# HighVoltageMeasurementModule_1000V_multi.net
KiCad netlist of a schematic drawn in EAGLE
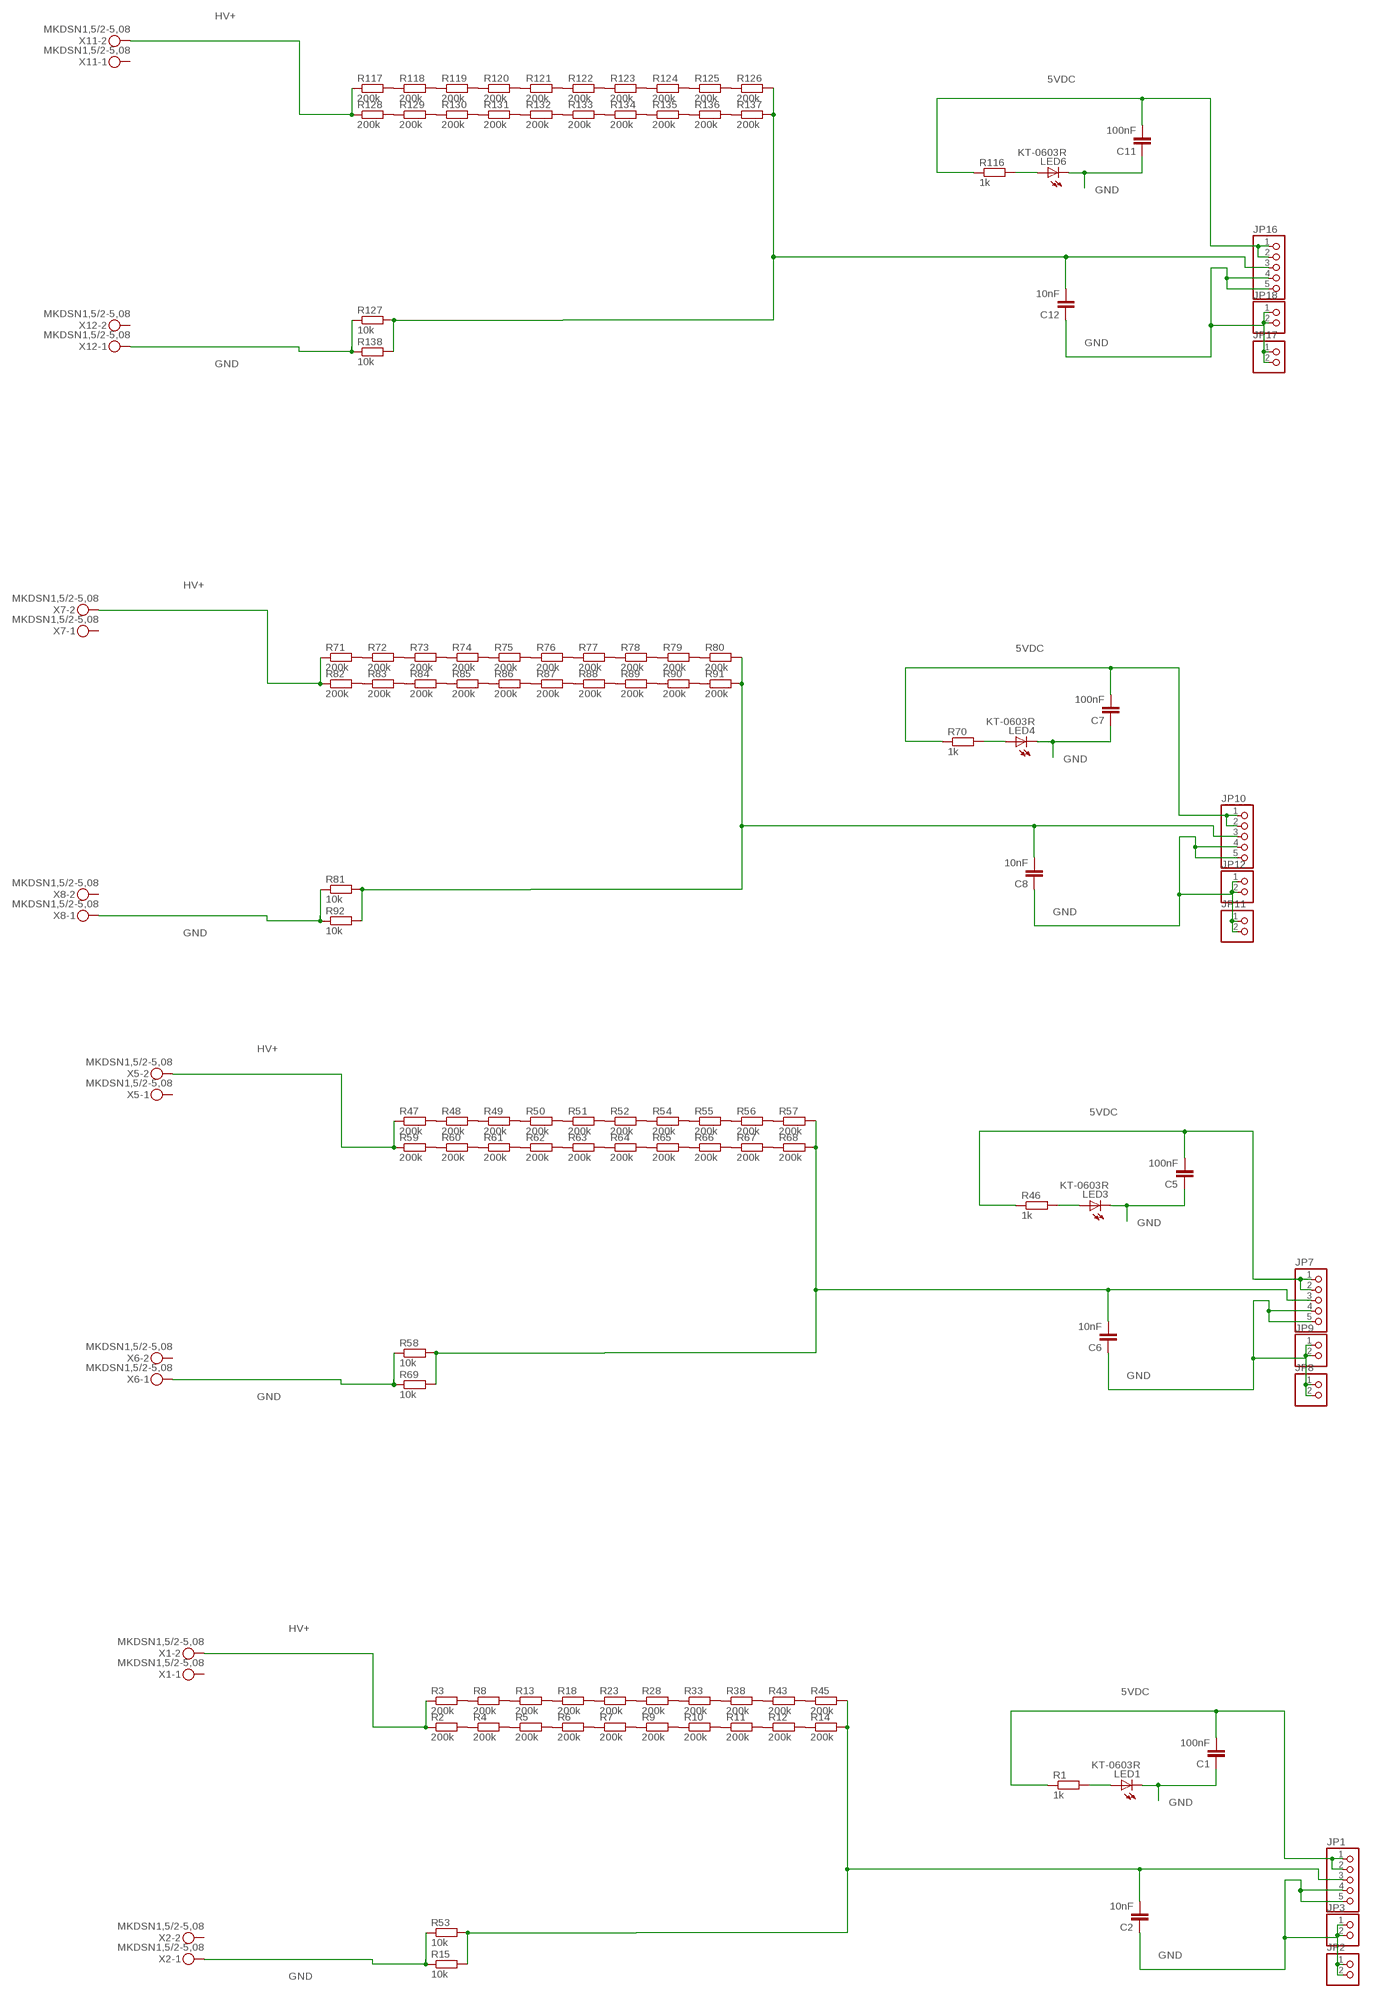
[diagram p0: schematic, sheet 1, part 1 of 2]
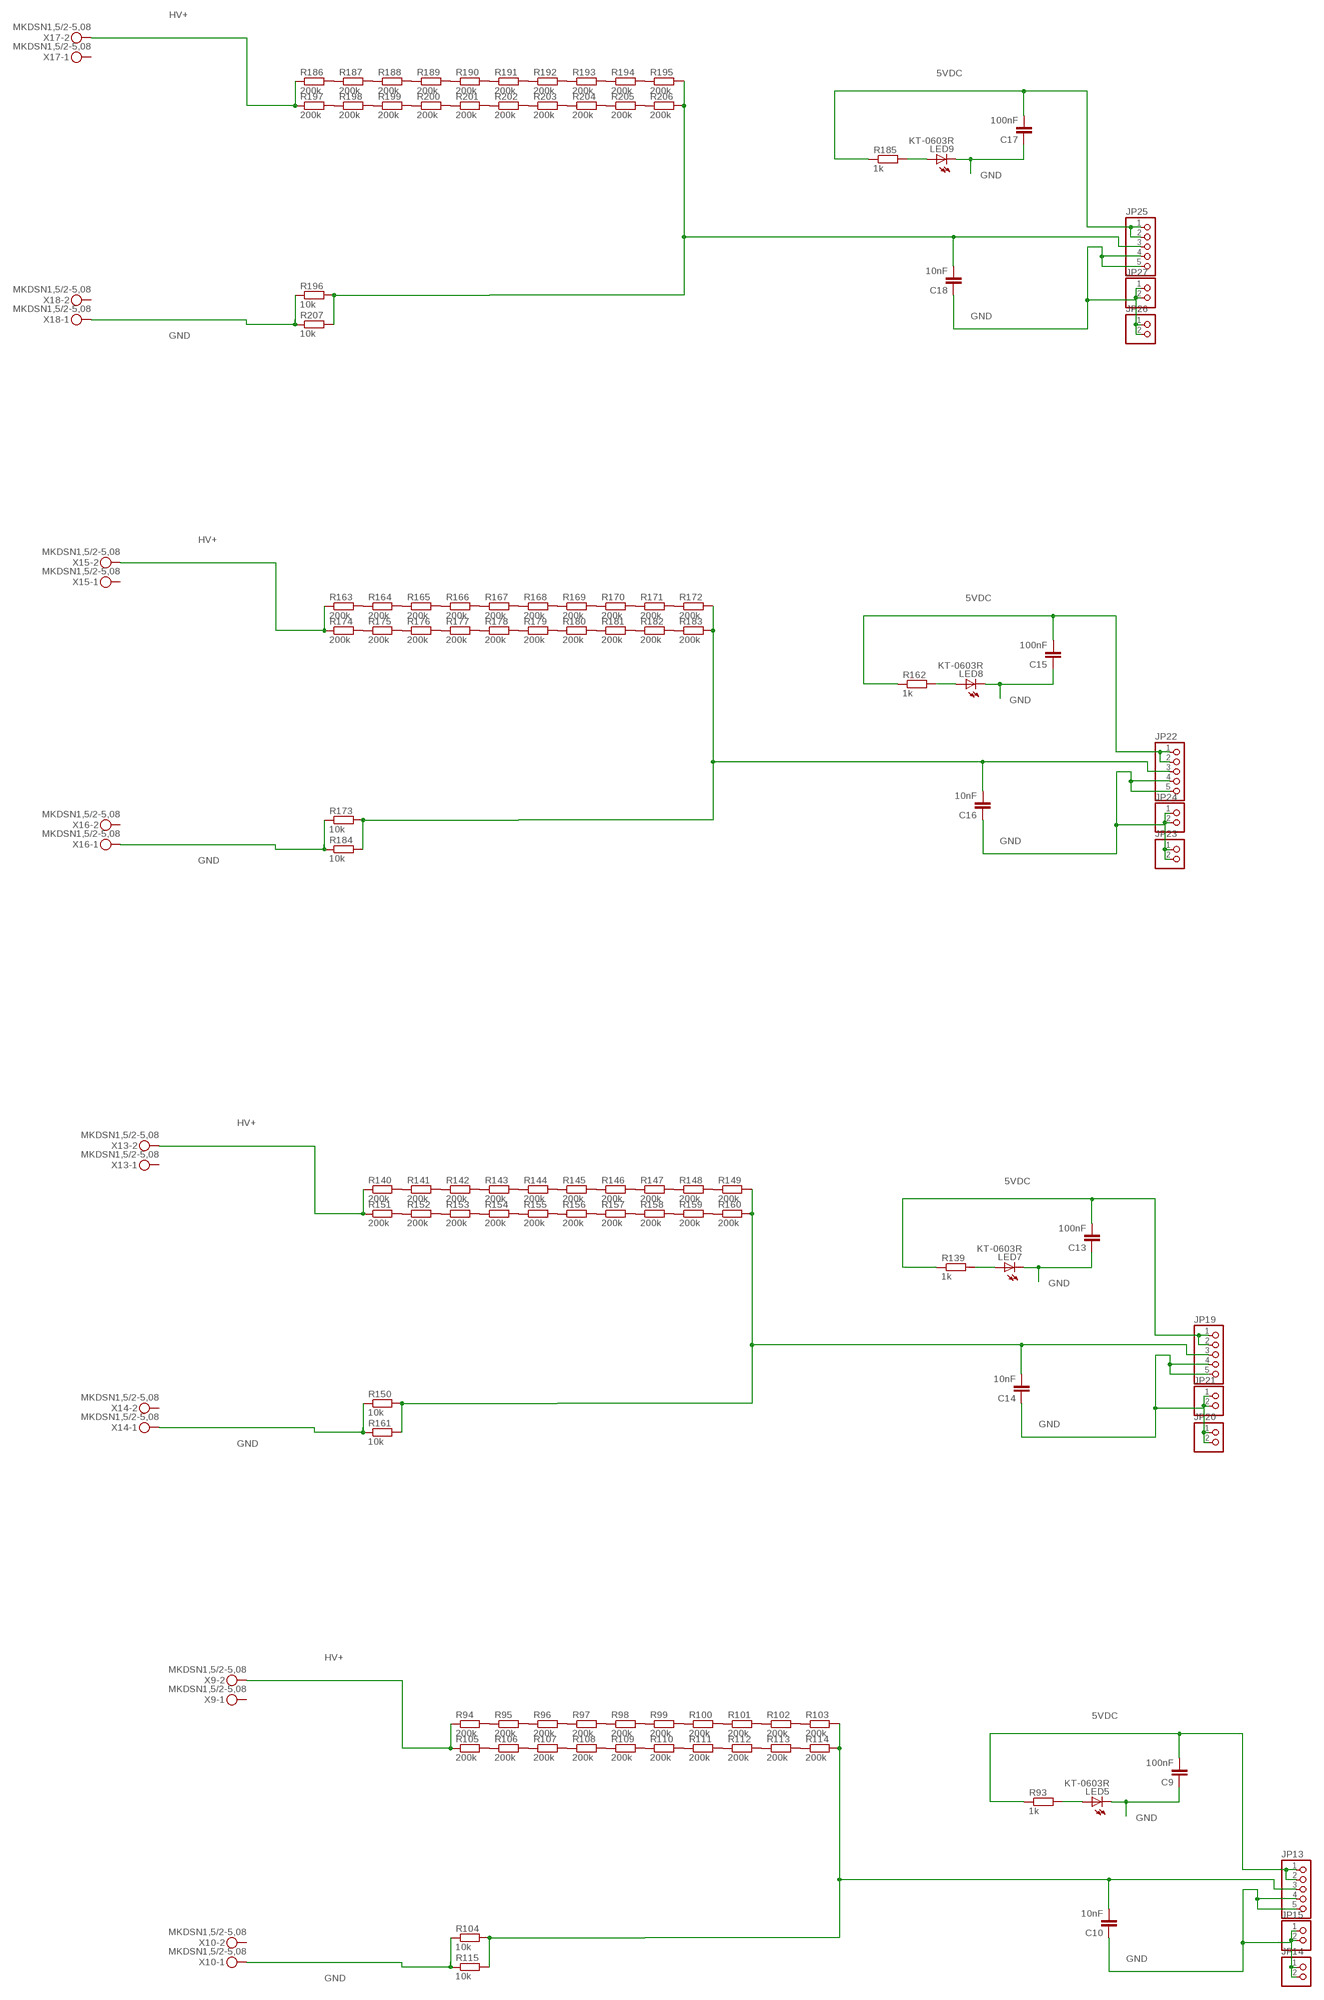
[diagram p1: schematic, sheet 1, part 2 of 2]

(export (version "E")
  (design (tool "Eeschema 10.0.6"))
  (components
    (comp (ref "C1")
      (value "100nF")
      (footprint "eagle-import:C0805")
      (libsource (lib "eagle-import") (part "C-EUC0805"))
    )
    (comp (ref "C2")
      (value "10nF")
      (footprint "eagle-import:C0805")
      (libsource (lib "eagle-import") (part "C-EUC0805"))
    )
    (comp (ref "C5")
      (value "100nF")
      (footprint "eagle-import:C0805")
      (libsource (lib "eagle-import") (part "C-EUC0805"))
    )
    (comp (ref "C6")
      (value "10nF")
      (footprint "eagle-import:C0805")
      (libsource (lib "eagle-import") (part "C-EUC0805"))
    )
    (comp (ref "C7")
      (value "100nF")
      (footprint "eagle-import:C0805")
      (libsource (lib "eagle-import") (part "C-EUC0805"))
    )
    (comp (ref "C8")
      (value "10nF")
      (footprint "eagle-import:C0805")
      (libsource (lib "eagle-import") (part "C-EUC0805"))
    )
    (comp (ref "C9")
      (value "100nF")
      (footprint "eagle-import:C0805")
      (libsource (lib "eagle-import") (part "C-EUC0805"))
    )
    (comp (ref "C10")
      (value "10nF")
      (footprint "eagle-import:C0805")
      (libsource (lib "eagle-import") (part "C-EUC0805"))
    )
    (comp (ref "C11")
      (value "100nF")
      (footprint "eagle-import:C0805")
      (libsource (lib "eagle-import") (part "C-EUC0805"))
    )
    (comp (ref "C12")
      (value "10nF")
      (footprint "eagle-import:C0805")
      (libsource (lib "eagle-import") (part "C-EUC0805"))
    )
    (comp (ref "C13")
      (value "100nF")
      (footprint "eagle-import:C0805")
      (libsource (lib "eagle-import") (part "C-EUC0805"))
    )
    (comp (ref "C14")
      (value "10nF")
      (footprint "eagle-import:C0805")
      (libsource (lib "eagle-import") (part "C-EUC0805"))
    )
    (comp (ref "C15")
      (value "100nF")
      (footprint "eagle-import:C0805")
      (libsource (lib "eagle-import") (part "C-EUC0805"))
    )
    (comp (ref "C16")
      (value "10nF")
      (footprint "eagle-import:C0805")
      (libsource (lib "eagle-import") (part "C-EUC0805"))
    )
    (comp (ref "C17")
      (value "100nF")
      (footprint "eagle-import:C0805")
      (libsource (lib "eagle-import") (part "C-EUC0805"))
    )
    (comp (ref "C18")
      (value "10nF")
      (footprint "eagle-import:C0805")
      (libsource (lib "eagle-import") (part "C-EUC0805"))
    )
    (comp (ref "JP1")
      (value "PINHD-1X5")
      (footprint "eagle-import:1X05")
      (libsource (lib "eagle-import") (part "PINHD-1X5"))
    )
    (comp (ref "JP2")
      (value "PINHD-1X2")
      (footprint "eagle-import:1X02")
      (libsource (lib "eagle-import") (part "PINHD-1X2"))
    )
    (comp (ref "JP3")
      (value "PINHD-1X2")
      (footprint "eagle-import:1X02")
      (libsource (lib "eagle-import") (part "PINHD-1X2"))
    )
    (comp (ref "JP7")
      (value "PINHD-1X5")
      (footprint "eagle-import:1X05")
      (libsource (lib "eagle-import") (part "PINHD-1X5"))
    )
    (comp (ref "JP8")
      (value "PINHD-1X2")
      (footprint "eagle-import:1X02")
      (libsource (lib "eagle-import") (part "PINHD-1X2"))
    )
    (comp (ref "JP9")
      (value "PINHD-1X2")
      (footprint "eagle-import:1X02")
      (libsource (lib "eagle-import") (part "PINHD-1X2"))
    )
    (comp (ref "JP10")
      (value "PINHD-1X5")
      (footprint "eagle-import:1X05")
      (libsource (lib "eagle-import") (part "PINHD-1X5"))
    )
    (comp (ref "JP11")
      (value "PINHD-1X2")
      (footprint "eagle-import:1X02")
      (libsource (lib "eagle-import") (part "PINHD-1X2"))
    )
    (comp (ref "JP12")
      (value "PINHD-1X2")
      (footprint "eagle-import:1X02")
      (libsource (lib "eagle-import") (part "PINHD-1X2"))
    )
    (comp (ref "JP13")
      (value "PINHD-1X5")
      (footprint "eagle-import:1X05")
      (libsource (lib "eagle-import") (part "PINHD-1X5"))
    )
    (comp (ref "JP14")
      (value "PINHD-1X2")
      (footprint "eagle-import:1X02")
      (libsource (lib "eagle-import") (part "PINHD-1X2"))
    )
    (comp (ref "JP15")
      (value "PINHD-1X2")
      (footprint "eagle-import:1X02")
      (libsource (lib "eagle-import") (part "PINHD-1X2"))
    )
    (comp (ref "JP16")
      (value "PINHD-1X5")
      (footprint "eagle-import:1X05")
      (libsource (lib "eagle-import") (part "PINHD-1X5"))
    )
    (comp (ref "JP17")
      (value "PINHD-1X2")
      (footprint "eagle-import:1X02")
      (libsource (lib "eagle-import") (part "PINHD-1X2"))
    )
    (comp (ref "JP18")
      (value "PINHD-1X2")
      (footprint "eagle-import:1X02")
      (libsource (lib "eagle-import") (part "PINHD-1X2"))
    )
    (comp (ref "JP19")
      (value "PINHD-1X5")
      (footprint "eagle-import:1X05")
      (libsource (lib "eagle-import") (part "PINHD-1X5"))
    )
    (comp (ref "JP20")
      (value "PINHD-1X2")
      (footprint "eagle-import:1X02")
      (libsource (lib "eagle-import") (part "PINHD-1X2"))
    )
    (comp (ref "JP21")
      (value "PINHD-1X2")
      (footprint "eagle-import:1X02")
      (libsource (lib "eagle-import") (part "PINHD-1X2"))
    )
    (comp (ref "JP22")
      (value "PINHD-1X5")
      (footprint "eagle-import:1X05")
      (libsource (lib "eagle-import") (part "PINHD-1X5"))
    )
    (comp (ref "JP23")
      (value "PINHD-1X2")
      (footprint "eagle-import:1X02")
      (libsource (lib "eagle-import") (part "PINHD-1X2"))
    )
    (comp (ref "JP24")
      (value "PINHD-1X2")
      (footprint "eagle-import:1X02")
      (libsource (lib "eagle-import") (part "PINHD-1X2"))
    )
    (comp (ref "JP25")
      (value "PINHD-1X5")
      (footprint "eagle-import:1X05")
      (libsource (lib "eagle-import") (part "PINHD-1X5"))
    )
    (comp (ref "JP26")
      (value "PINHD-1X2")
      (footprint "eagle-import:1X02")
      (libsource (lib "eagle-import") (part "PINHD-1X2"))
    )
    (comp (ref "JP27")
      (value "PINHD-1X2")
      (footprint "eagle-import:1X02")
      (libsource (lib "eagle-import") (part "PINHD-1X2"))
    )
    (comp (ref "LED1")
      (value "KT-0603R")
      (footprint "eagle-import:CHIPLED_0603")
      (libsource (lib "eagle-import") (part "LEDCHIPLED_0603"))
    )
    (comp (ref "LED3")
      (value "KT-0603R")
      (footprint "eagle-import:CHIPLED_0603")
      (libsource (lib "eagle-import") (part "LEDCHIPLED_0603"))
    )
    (comp (ref "LED4")
      (value "KT-0603R")
      (footprint "eagle-import:CHIPLED_0603")
      (libsource (lib "eagle-import") (part "LEDCHIPLED_0603"))
    )
    (comp (ref "LED5")
      (value "KT-0603R")
      (footprint "eagle-import:CHIPLED_0603")
      (libsource (lib "eagle-import") (part "LEDCHIPLED_0603"))
    )
    (comp (ref "LED6")
      (value "KT-0603R")
      (footprint "eagle-import:CHIPLED_0603")
      (libsource (lib "eagle-import") (part "LEDCHIPLED_0603"))
    )
    (comp (ref "LED7")
      (value "KT-0603R")
      (footprint "eagle-import:CHIPLED_0603")
      (libsource (lib "eagle-import") (part "LEDCHIPLED_0603"))
    )
    (comp (ref "LED8")
      (value "KT-0603R")
      (footprint "eagle-import:CHIPLED_0603")
      (libsource (lib "eagle-import") (part "LEDCHIPLED_0603"))
    )
    (comp (ref "LED9")
      (value "KT-0603R")
      (footprint "eagle-import:CHIPLED_0603")
      (libsource (lib "eagle-import") (part "LEDCHIPLED_0603"))
    )
    (comp (ref "R1")
      (value "1k")
      (footprint "eagle-import:R0805")
      (libsource (lib "eagle-import") (part "R-EU_R0805"))
    )
    (comp (ref "R2")
      (value "200k")
      (footprint "eagle-import:R0805")
      (libsource (lib "eagle-import") (part "R-EU_R0805"))
    )
    (comp (ref "R3")
      (value "200k")
      (footprint "eagle-import:R0805")
      (libsource (lib "eagle-import") (part "R-EU_R0805"))
    )
    (comp (ref "R4")
      (value "200k")
      (footprint "eagle-import:R0805")
      (libsource (lib "eagle-import") (part "R-EU_R0805"))
    )
    (comp (ref "R5")
      (value "200k")
      (footprint "eagle-import:R0805")
      (libsource (lib "eagle-import") (part "R-EU_R0805"))
    )
    (comp (ref "R6")
      (value "200k")
      (footprint "eagle-import:R0805")
      (libsource (lib "eagle-import") (part "R-EU_R0805"))
    )
    (comp (ref "R7")
      (value "200k")
      (footprint "eagle-import:R0805")
      (libsource (lib "eagle-import") (part "R-EU_R0805"))
    )
    (comp (ref "R8")
      (value "200k")
      (footprint "eagle-import:R0805")
      (libsource (lib "eagle-import") (part "R-EU_R0805"))
    )
    (comp (ref "R9")
      (value "200k")
      (footprint "eagle-import:R0805")
      (libsource (lib "eagle-import") (part "R-EU_R0805"))
    )
    (comp (ref "R10")
      (value "200k")
      (footprint "eagle-import:R0805")
      (libsource (lib "eagle-import") (part "R-EU_R0805"))
    )
    (comp (ref "R11")
      (value "200k")
      (footprint "eagle-import:R0805")
      (libsource (lib "eagle-import") (part "R-EU_R0805"))
    )
    (comp (ref "R12")
      (value "200k")
      (footprint "eagle-import:R0805")
      (libsource (lib "eagle-import") (part "R-EU_R0805"))
    )
    (comp (ref "R13")
      (value "200k")
      (footprint "eagle-import:R0805")
      (libsource (lib "eagle-import") (part "R-EU_R0805"))
    )
    (comp (ref "R14")
      (value "200k")
      (footprint "eagle-import:R0805")
      (libsource (lib "eagle-import") (part "R-EU_R0805"))
    )
    (comp (ref "R15")
      (value "10k")
      (footprint "eagle-import:R0805")
      (libsource (lib "eagle-import") (part "R-EU_R0805"))
    )
    (comp (ref "R18")
      (value "200k")
      (footprint "eagle-import:R0805")
      (libsource (lib "eagle-import") (part "R-EU_R0805"))
    )
    (comp (ref "R23")
      (value "200k")
      (footprint "eagle-import:R0805")
      (libsource (lib "eagle-import") (part "R-EU_R0805"))
    )
    (comp (ref "R28")
      (value "200k")
      (footprint "eagle-import:R0805")
      (libsource (lib "eagle-import") (part "R-EU_R0805"))
    )
    (comp (ref "R33")
      (value "200k")
      (footprint "eagle-import:R0805")
      (libsource (lib "eagle-import") (part "R-EU_R0805"))
    )
    (comp (ref "R38")
      (value "200k")
      (footprint "eagle-import:R0805")
      (libsource (lib "eagle-import") (part "R-EU_R0805"))
    )
    (comp (ref "R43")
      (value "200k")
      (footprint "eagle-import:R0805")
      (libsource (lib "eagle-import") (part "R-EU_R0805"))
    )
    (comp (ref "R45")
      (value "200k")
      (footprint "eagle-import:R0805")
      (libsource (lib "eagle-import") (part "R-EU_R0805"))
    )
    (comp (ref "R46")
      (value "1k")
      (footprint "eagle-import:R0805")
      (libsource (lib "eagle-import") (part "R-EU_R0805"))
    )
    (comp (ref "R47")
      (value "200k")
      (footprint "eagle-import:R0805")
      (libsource (lib "eagle-import") (part "R-EU_R0805"))
    )
    (comp (ref "R48")
      (value "200k")
      (footprint "eagle-import:R0805")
      (libsource (lib "eagle-import") (part "R-EU_R0805"))
    )
    (comp (ref "R49")
      (value "200k")
      (footprint "eagle-import:R0805")
      (libsource (lib "eagle-import") (part "R-EU_R0805"))
    )
    (comp (ref "R50")
      (value "200k")
      (footprint "eagle-import:R0805")
      (libsource (lib "eagle-import") (part "R-EU_R0805"))
    )
    (comp (ref "R51")
      (value "200k")
      (footprint "eagle-import:R0805")
      (libsource (lib "eagle-import") (part "R-EU_R0805"))
    )
    (comp (ref "R52")
      (value "200k")
      (footprint "eagle-import:R0805")
      (libsource (lib "eagle-import") (part "R-EU_R0805"))
    )
    (comp (ref "R53")
      (value "10k")
      (footprint "eagle-import:R0805")
      (libsource (lib "eagle-import") (part "R-EU_R0805"))
    )
    (comp (ref "R54")
      (value "200k")
      (footprint "eagle-import:R0805")
      (libsource (lib "eagle-import") (part "R-EU_R0805"))
    )
    (comp (ref "R55")
      (value "200k")
      (footprint "eagle-import:R0805")
      (libsource (lib "eagle-import") (part "R-EU_R0805"))
    )
    (comp (ref "R56")
      (value "200k")
      (footprint "eagle-import:R0805")
      (libsource (lib "eagle-import") (part "R-EU_R0805"))
    )
    (comp (ref "R57")
      (value "200k")
      (footprint "eagle-import:R0805")
      (libsource (lib "eagle-import") (part "R-EU_R0805"))
    )
    (comp (ref "R58")
      (value "10k")
      (footprint "eagle-import:R0805")
      (libsource (lib "eagle-import") (part "R-EU_R0805"))
    )
    (comp (ref "R59")
      (value "200k")
      (footprint "eagle-import:R0805")
      (libsource (lib "eagle-import") (part "R-EU_R0805"))
    )
    (comp (ref "R60")
      (value "200k")
      (footprint "eagle-import:R0805")
      (libsource (lib "eagle-import") (part "R-EU_R0805"))
    )
    (comp (ref "R61")
      (value "200k")
      (footprint "eagle-import:R0805")
      (libsource (lib "eagle-import") (part "R-EU_R0805"))
    )
    (comp (ref "R62")
      (value "200k")
      (footprint "eagle-import:R0805")
      (libsource (lib "eagle-import") (part "R-EU_R0805"))
    )
    (comp (ref "R63")
      (value "200k")
      (footprint "eagle-import:R0805")
      (libsource (lib "eagle-import") (part "R-EU_R0805"))
    )
    (comp (ref "R64")
      (value "200k")
      (footprint "eagle-import:R0805")
      (libsource (lib "eagle-import") (part "R-EU_R0805"))
    )
    (comp (ref "R65")
      (value "200k")
      (footprint "eagle-import:R0805")
      (libsource (lib "eagle-import") (part "R-EU_R0805"))
    )
    (comp (ref "R66")
      (value "200k")
      (footprint "eagle-import:R0805")
      (libsource (lib "eagle-import") (part "R-EU_R0805"))
    )
    (comp (ref "R67")
      (value "200k")
      (footprint "eagle-import:R0805")
      (libsource (lib "eagle-import") (part "R-EU_R0805"))
    )
    (comp (ref "R68")
      (value "200k")
      (footprint "eagle-import:R0805")
      (libsource (lib "eagle-import") (part "R-EU_R0805"))
    )
    (comp (ref "R69")
      (value "10k")
      (footprint "eagle-import:R0805")
      (libsource (lib "eagle-import") (part "R-EU_R0805"))
    )
    (comp (ref "R70")
      (value "1k")
      (footprint "eagle-import:R0805")
      (libsource (lib "eagle-import") (part "R-EU_R0805"))
    )
    (comp (ref "R71")
      (value "200k")
      (footprint "eagle-import:R0805")
      (libsource (lib "eagle-import") (part "R-EU_R0805"))
    )
    (comp (ref "R72")
      (value "200k")
      (footprint "eagle-import:R0805")
      (libsource (lib "eagle-import") (part "R-EU_R0805"))
    )
    (comp (ref "R73")
      (value "200k")
      (footprint "eagle-import:R0805")
      (libsource (lib "eagle-import") (part "R-EU_R0805"))
    )
    (comp (ref "R74")
      (value "200k")
      (footprint "eagle-import:R0805")
      (libsource (lib "eagle-import") (part "R-EU_R0805"))
    )
    (comp (ref "R75")
      (value "200k")
      (footprint "eagle-import:R0805")
      (libsource (lib "eagle-import") (part "R-EU_R0805"))
    )
    (comp (ref "R76")
      (value "200k")
      (footprint "eagle-import:R0805")
      (libsource (lib "eagle-import") (part "R-EU_R0805"))
    )
    (comp (ref "R77")
      (value "200k")
      (footprint "eagle-import:R0805")
      (libsource (lib "eagle-import") (part "R-EU_R0805"))
    )
    (comp (ref "R78")
      (value "200k")
      (footprint "eagle-import:R0805")
      (libsource (lib "eagle-import") (part "R-EU_R0805"))
    )
    (comp (ref "R79")
      (value "200k")
      (footprint "eagle-import:R0805")
      (libsource (lib "eagle-import") (part "R-EU_R0805"))
    )
    (comp (ref "R80")
      (value "200k")
      (footprint "eagle-import:R0805")
      (libsource (lib "eagle-import") (part "R-EU_R0805"))
    )
    (comp (ref "R81")
      (value "10k")
      (footprint "eagle-import:R0805")
      (libsource (lib "eagle-import") (part "R-EU_R0805"))
    )
    (comp (ref "R82")
      (value "200k")
      (footprint "eagle-import:R0805")
      (libsource (lib "eagle-import") (part "R-EU_R0805"))
    )
    (comp (ref "R83")
      (value "200k")
      (footprint "eagle-import:R0805")
      (libsource (lib "eagle-import") (part "R-EU_R0805"))
    )
    (comp (ref "R84")
      (value "200k")
      (footprint "eagle-import:R0805")
      (libsource (lib "eagle-import") (part "R-EU_R0805"))
    )
    (comp (ref "R85")
      (value "200k")
      (footprint "eagle-import:R0805")
      (libsource (lib "eagle-import") (part "R-EU_R0805"))
    )
    (comp (ref "R86")
      (value "200k")
      (footprint "eagle-import:R0805")
      (libsource (lib "eagle-import") (part "R-EU_R0805"))
    )
    (comp (ref "R87")
      (value "200k")
      (footprint "eagle-import:R0805")
      (libsource (lib "eagle-import") (part "R-EU_R0805"))
    )
    (comp (ref "R88")
      (value "200k")
      (footprint "eagle-import:R0805")
      (libsource (lib "eagle-import") (part "R-EU_R0805"))
    )
    (comp (ref "R89")
      (value "200k")
      (footprint "eagle-import:R0805")
      (libsource (lib "eagle-import") (part "R-EU_R0805"))
    )
    (comp (ref "R90")
      (value "200k")
      (footprint "eagle-import:R0805")
      (libsource (lib "eagle-import") (part "R-EU_R0805"))
    )
    (comp (ref "R91")
      (value "200k")
      (footprint "eagle-import:R0805")
      (libsource (lib "eagle-import") (part "R-EU_R0805"))
    )
    (comp (ref "R92")
      (value "10k")
      (footprint "eagle-import:R0805")
      (libsource (lib "eagle-import") (part "R-EU_R0805"))
    )
    (comp (ref "R93")
      (value "1k")
      (footprint "eagle-import:R0805")
      (libsource (lib "eagle-import") (part "R-EU_R0805"))
    )
    (comp (ref "R94")
      (value "200k")
      (footprint "eagle-import:R0805")
      (libsource (lib "eagle-import") (part "R-EU_R0805"))
    )
    (comp (ref "R95")
      (value "200k")
      (footprint "eagle-import:R0805")
      (libsource (lib "eagle-import") (part "R-EU_R0805"))
    )
    (comp (ref "R96")
      (value "200k")
      (footprint "eagle-import:R0805")
      (libsource (lib "eagle-import") (part "R-EU_R0805"))
    )
    (comp (ref "R97")
      (value "200k")
      (footprint "eagle-import:R0805")
      (libsource (lib "eagle-import") (part "R-EU_R0805"))
    )
    (comp (ref "R98")
      (value "200k")
      (footprint "eagle-import:R0805")
      (libsource (lib "eagle-import") (part "R-EU_R0805"))
    )
    (comp (ref "R99")
      (value "200k")
      (footprint "eagle-import:R0805")
      (libsource (lib "eagle-import") (part "R-EU_R0805"))
    )
    (comp (ref "R100")
      (value "200k")
      (footprint "eagle-import:R0805")
      (libsource (lib "eagle-import") (part "R-EU_R0805"))
    )
    (comp (ref "R101")
      (value "200k")
      (footprint "eagle-import:R0805")
      (libsource (lib "eagle-import") (part "R-EU_R0805"))
    )
    (comp (ref "R102")
      (value "200k")
      (footprint "eagle-import:R0805")
      (libsource (lib "eagle-import") (part "R-EU_R0805"))
    )
    (comp (ref "R103")
      (value "200k")
      (footprint "eagle-import:R0805")
      (libsource (lib "eagle-import") (part "R-EU_R0805"))
    )
    (comp (ref "R104")
      (value "10k")
      (footprint "eagle-import:R0805")
      (libsource (lib "eagle-import") (part "R-EU_R0805"))
    )
    (comp (ref "R105")
      (value "200k")
      (footprint "eagle-import:R0805")
      (libsource (lib "eagle-import") (part "R-EU_R0805"))
    )
    (comp (ref "R106")
      (value "200k")
      (footprint "eagle-import:R0805")
      (libsource (lib "eagle-import") (part "R-EU_R0805"))
    )
    (comp (ref "R107")
      (value "200k")
      (footprint "eagle-import:R0805")
      (libsource (lib "eagle-import") (part "R-EU_R0805"))
    )
    (comp (ref "R108")
      (value "200k")
      (footprint "eagle-import:R0805")
      (libsource (lib "eagle-import") (part "R-EU_R0805"))
    )
    (comp (ref "R109")
      (value "200k")
      (footprint "eagle-import:R0805")
      (libsource (lib "eagle-import") (part "R-EU_R0805"))
    )
    (comp (ref "R110")
      (value "200k")
      (footprint "eagle-import:R0805")
      (libsource (lib "eagle-import") (part "R-EU_R0805"))
    )
    (comp (ref "R111")
      (value "200k")
      (footprint "eagle-import:R0805")
      (libsource (lib "eagle-import") (part "R-EU_R0805"))
    )
    (comp (ref "R112")
      (value "200k")
      (footprint "eagle-import:R0805")
      (libsource (lib "eagle-import") (part "R-EU_R0805"))
    )
    (comp (ref "R113")
      (value "200k")
      (footprint "eagle-import:R0805")
      (libsource (lib "eagle-import") (part "R-EU_R0805"))
    )
    (comp (ref "R114")
      (value "200k")
      (footprint "eagle-import:R0805")
      (libsource (lib "eagle-import") (part "R-EU_R0805"))
    )
    (comp (ref "R115")
      (value "10k")
      (footprint "eagle-import:R0805")
      (libsource (lib "eagle-import") (part "R-EU_R0805"))
    )
    (comp (ref "R116")
      (value "1k")
      (footprint "eagle-import:R0805")
      (libsource (lib "eagle-import") (part "R-EU_R0805"))
    )
    (comp (ref "R117")
      (value "200k")
      (footprint "eagle-import:R0805")
      (libsource (lib "eagle-import") (part "R-EU_R0805"))
    )
    (comp (ref "R118")
      (value "200k")
      (footprint "eagle-import:R0805")
      (libsource (lib "eagle-import") (part "R-EU_R0805"))
    )
    (comp (ref "R119")
      (value "200k")
      (footprint "eagle-import:R0805")
      (libsource (lib "eagle-import") (part "R-EU_R0805"))
    )
    (comp (ref "R120")
      (value "200k")
      (footprint "eagle-import:R0805")
      (libsource (lib "eagle-import") (part "R-EU_R0805"))
    )
    (comp (ref "R121")
      (value "200k")
      (footprint "eagle-import:R0805")
      (libsource (lib "eagle-import") (part "R-EU_R0805"))
    )
    (comp (ref "R122")
      (value "200k")
      (footprint "eagle-import:R0805")
      (libsource (lib "eagle-import") (part "R-EU_R0805"))
    )
    (comp (ref "R123")
      (value "200k")
      (footprint "eagle-import:R0805")
      (libsource (lib "eagle-import") (part "R-EU_R0805"))
    )
    (comp (ref "R124")
      (value "200k")
      (footprint "eagle-import:R0805")
      (libsource (lib "eagle-import") (part "R-EU_R0805"))
    )
    (comp (ref "R125")
      (value "200k")
      (footprint "eagle-import:R0805")
      (libsource (lib "eagle-import") (part "R-EU_R0805"))
    )
    (comp (ref "R126")
      (value "200k")
      (footprint "eagle-import:R0805")
      (libsource (lib "eagle-import") (part "R-EU_R0805"))
    )
    (comp (ref "R127")
      (value "10k")
      (footprint "eagle-import:R0805")
      (libsource (lib "eagle-import") (part "R-EU_R0805"))
    )
    (comp (ref "R128")
      (value "200k")
      (footprint "eagle-import:R0805")
      (libsource (lib "eagle-import") (part "R-EU_R0805"))
    )
    (comp (ref "R129")
      (value "200k")
      (footprint "eagle-import:R0805")
      (libsource (lib "eagle-import") (part "R-EU_R0805"))
    )
    (comp (ref "R130")
      (value "200k")
      (footprint "eagle-import:R0805")
      (libsource (lib "eagle-import") (part "R-EU_R0805"))
    )
    (comp (ref "R131")
      (value "200k")
      (footprint "eagle-import:R0805")
      (libsource (lib "eagle-import") (part "R-EU_R0805"))
    )
    (comp (ref "R132")
      (value "200k")
      (footprint "eagle-import:R0805")
      (libsource (lib "eagle-import") (part "R-EU_R0805"))
    )
    (comp (ref "R133")
      (value "200k")
      (footprint "eagle-import:R0805")
      (libsource (lib "eagle-import") (part "R-EU_R0805"))
    )
    (comp (ref "R134")
      (value "200k")
      (footprint "eagle-import:R0805")
      (libsource (lib "eagle-import") (part "R-EU_R0805"))
    )
    (comp (ref "R135")
      (value "200k")
      (footprint "eagle-import:R0805")
      (libsource (lib "eagle-import") (part "R-EU_R0805"))
    )
    (comp (ref "R136")
      (value "200k")
      (footprint "eagle-import:R0805")
      (libsource (lib "eagle-import") (part "R-EU_R0805"))
    )
    (comp (ref "R137")
      (value "200k")
      (footprint "eagle-import:R0805")
      (libsource (lib "eagle-import") (part "R-EU_R0805"))
    )
    (comp (ref "R138")
      (value "10k")
      (footprint "eagle-import:R0805")
      (libsource (lib "eagle-import") (part "R-EU_R0805"))
    )
    (comp (ref "R139")
      (value "1k")
      (footprint "eagle-import:R0805")
      (libsource (lib "eagle-import") (part "R-EU_R0805"))
    )
    (comp (ref "R140")
      (value "200k")
      (footprint "eagle-import:R0805")
      (libsource (lib "eagle-import") (part "R-EU_R0805"))
    )
    (comp (ref "R141")
      (value "200k")
      (footprint "eagle-import:R0805")
      (libsource (lib "eagle-import") (part "R-EU_R0805"))
    )
    (comp (ref "R142")
      (value "200k")
      (footprint "eagle-import:R0805")
      (libsource (lib "eagle-import") (part "R-EU_R0805"))
    )
    (comp (ref "R143")
      (value "200k")
      (footprint "eagle-import:R0805")
      (libsource (lib "eagle-import") (part "R-EU_R0805"))
    )
    (comp (ref "R144")
      (value "200k")
      (footprint "eagle-import:R0805")
      (libsource (lib "eagle-import") (part "R-EU_R0805"))
    )
    (comp (ref "R145")
      (value "200k")
      (footprint "eagle-import:R0805")
      (libsource (lib "eagle-import") (part "R-EU_R0805"))
    )
    (comp (ref "R146")
      (value "200k")
      (footprint "eagle-import:R0805")
      (libsource (lib "eagle-import") (part "R-EU_R0805"))
    )
    (comp (ref "R147")
      (value "200k")
      (footprint "eagle-import:R0805")
      (libsource (lib "eagle-import") (part "R-EU_R0805"))
    )
    (comp (ref "R148")
      (value "200k")
      (footprint "eagle-import:R0805")
      (libsource (lib "eagle-import") (part "R-EU_R0805"))
    )
    (comp (ref "R149")
      (value "200k")
      (footprint "eagle-import:R0805")
      (libsource (lib "eagle-import") (part "R-EU_R0805"))
    )
    (comp (ref "R150")
      (value "10k")
      (footprint "eagle-import:R0805")
      (libsource (lib "eagle-import") (part "R-EU_R0805"))
    )
    (comp (ref "R151")
      (value "200k")
      (footprint "eagle-import:R0805")
      (libsource (lib "eagle-import") (part "R-EU_R0805"))
    )
    (comp (ref "R152")
      (value "200k")
      (footprint "eagle-import:R0805")
      (libsource (lib "eagle-import") (part "R-EU_R0805"))
    )
    (comp (ref "R153")
      (value "200k")
      (footprint "eagle-import:R0805")
      (libsource (lib "eagle-import") (part "R-EU_R0805"))
    )
    (comp (ref "R154")
      (value "200k")
      (footprint "eagle-import:R0805")
      (libsource (lib "eagle-import") (part "R-EU_R0805"))
    )
    (comp (ref "R155")
      (value "200k")
      (footprint "eagle-import:R0805")
      (libsource (lib "eagle-import") (part "R-EU_R0805"))
    )
    (comp (ref "R156")
      (value "200k")
      (footprint "eagle-import:R0805")
      (libsource (lib "eagle-import") (part "R-EU_R0805"))
    )
    (comp (ref "R157")
      (value "200k")
      (footprint "eagle-import:R0805")
      (libsource (lib "eagle-import") (part "R-EU_R0805"))
    )
    (comp (ref "R158")
      (value "200k")
      (footprint "eagle-import:R0805")
      (libsource (lib "eagle-import") (part "R-EU_R0805"))
    )
    (comp (ref "R159")
      (value "200k")
      (footprint "eagle-import:R0805")
      (libsource (lib "eagle-import") (part "R-EU_R0805"))
    )
    (comp (ref "R160")
      (value "200k")
      (footprint "eagle-import:R0805")
      (libsource (lib "eagle-import") (part "R-EU_R0805"))
    )
    (comp (ref "R161")
      (value "10k")
      (footprint "eagle-import:R0805")
      (libsource (lib "eagle-import") (part "R-EU_R0805"))
    )
    (comp (ref "R162")
      (value "1k")
      (footprint "eagle-import:R0805")
      (libsource (lib "eagle-import") (part "R-EU_R0805"))
    )
    (comp (ref "R163")
      (value "200k")
      (footprint "eagle-import:R0805")
      (libsource (lib "eagle-import") (part "R-EU_R0805"))
    )
    (comp (ref "R164")
      (value "200k")
      (footprint "eagle-import:R0805")
      (libsource (lib "eagle-import") (part "R-EU_R0805"))
    )
    (comp (ref "R165")
      (value "200k")
      (footprint "eagle-import:R0805")
      (libsource (lib "eagle-import") (part "R-EU_R0805"))
    )
    (comp (ref "R166")
      (value "200k")
      (footprint "eagle-import:R0805")
      (libsource (lib "eagle-import") (part "R-EU_R0805"))
    )
    (comp (ref "R167")
      (value "200k")
      (footprint "eagle-import:R0805")
      (libsource (lib "eagle-import") (part "R-EU_R0805"))
    )
    (comp (ref "R168")
      (value "200k")
      (footprint "eagle-import:R0805")
      (libsource (lib "eagle-import") (part "R-EU_R0805"))
    )
    (comp (ref "R169")
      (value "200k")
      (footprint "eagle-import:R0805")
      (libsource (lib "eagle-import") (part "R-EU_R0805"))
    )
    (comp (ref "R170")
      (value "200k")
      (footprint "eagle-import:R0805")
      (libsource (lib "eagle-import") (part "R-EU_R0805"))
    )
    (comp (ref "R171")
      (value "200k")
      (footprint "eagle-import:R0805")
      (libsource (lib "eagle-import") (part "R-EU_R0805"))
    )
    (comp (ref "R172")
      (value "200k")
      (footprint "eagle-import:R0805")
      (libsource (lib "eagle-import") (part "R-EU_R0805"))
    )
    (comp (ref "R173")
      (value "10k")
      (footprint "eagle-import:R0805")
      (libsource (lib "eagle-import") (part "R-EU_R0805"))
    )
    (comp (ref "R174")
      (value "200k")
      (footprint "eagle-import:R0805")
      (libsource (lib "eagle-import") (part "R-EU_R0805"))
    )
    (comp (ref "R175")
      (value "200k")
      (footprint "eagle-import:R0805")
      (libsource (lib "eagle-import") (part "R-EU_R0805"))
    )
    (comp (ref "R176")
      (value "200k")
      (footprint "eagle-import:R0805")
      (libsource (lib "eagle-import") (part "R-EU_R0805"))
    )
    (comp (ref "R177")
      (value "200k")
      (footprint "eagle-import:R0805")
      (libsource (lib "eagle-import") (part "R-EU_R0805"))
    )
    (comp (ref "R178")
      (value "200k")
      (footprint "eagle-import:R0805")
      (libsource (lib "eagle-import") (part "R-EU_R0805"))
    )
    (comp (ref "R179")
      (value "200k")
      (footprint "eagle-import:R0805")
      (libsource (lib "eagle-import") (part "R-EU_R0805"))
    )
    (comp (ref "R180")
      (value "200k")
      (footprint "eagle-import:R0805")
      (libsource (lib "eagle-import") (part "R-EU_R0805"))
    )
    (comp (ref "R181")
      (value "200k")
      (footprint "eagle-import:R0805")
      (libsource (lib "eagle-import") (part "R-EU_R0805"))
    )
    (comp (ref "R182")
      (value "200k")
      (footprint "eagle-import:R0805")
      (libsource (lib "eagle-import") (part "R-EU_R0805"))
    )
    (comp (ref "R183")
      (value "200k")
      (footprint "eagle-import:R0805")
      (libsource (lib "eagle-import") (part "R-EU_R0805"))
    )
    (comp (ref "R184")
      (value "10k")
      (footprint "eagle-import:R0805")
      (libsource (lib "eagle-import") (part "R-EU_R0805"))
    )
    (comp (ref "R185")
      (value "1k")
      (footprint "eagle-import:R0805")
      (libsource (lib "eagle-import") (part "R-EU_R0805"))
    )
    (comp (ref "R186")
      (value "200k")
      (footprint "eagle-import:R0805")
      (libsource (lib "eagle-import") (part "R-EU_R0805"))
    )
    (comp (ref "R187")
      (value "200k")
      (footprint "eagle-import:R0805")
      (libsource (lib "eagle-import") (part "R-EU_R0805"))
    )
    (comp (ref "R188")
      (value "200k")
      (footprint "eagle-import:R0805")
      (libsource (lib "eagle-import") (part "R-EU_R0805"))
    )
    (comp (ref "R189")
      (value "200k")
      (footprint "eagle-import:R0805")
      (libsource (lib "eagle-import") (part "R-EU_R0805"))
    )
    (comp (ref "R190")
      (value "200k")
      (footprint "eagle-import:R0805")
      (libsource (lib "eagle-import") (part "R-EU_R0805"))
    )
    (comp (ref "R191")
      (value "200k")
      (footprint "eagle-import:R0805")
      (libsource (lib "eagle-import") (part "R-EU_R0805"))
    )
    (comp (ref "R192")
      (value "200k")
      (footprint "eagle-import:R0805")
      (libsource (lib "eagle-import") (part "R-EU_R0805"))
    )
    (comp (ref "R193")
      (value "200k")
      (footprint "eagle-import:R0805")
      (libsource (lib "eagle-import") (part "R-EU_R0805"))
    )
    (comp (ref "R194")
      (value "200k")
      (footprint "eagle-import:R0805")
      (libsource (lib "eagle-import") (part "R-EU_R0805"))
    )
    (comp (ref "R195")
      (value "200k")
      (footprint "eagle-import:R0805")
      (libsource (lib "eagle-import") (part "R-EU_R0805"))
    )
    (comp (ref "R196")
      (value "10k")
      (footprint "eagle-import:R0805")
      (libsource (lib "eagle-import") (part "R-EU_R0805"))
    )
    (comp (ref "R197")
      (value "200k")
      (footprint "eagle-import:R0805")
      (libsource (lib "eagle-import") (part "R-EU_R0805"))
    )
    (comp (ref "R198")
      (value "200k")
      (footprint "eagle-import:R0805")
      (libsource (lib "eagle-import") (part "R-EU_R0805"))
    )
    (comp (ref "R199")
      (value "200k")
      (footprint "eagle-import:R0805")
      (libsource (lib "eagle-import") (part "R-EU_R0805"))
    )
    (comp (ref "R200")
      (value "200k")
      (footprint "eagle-import:R0805")
      (libsource (lib "eagle-import") (part "R-EU_R0805"))
    )
    (comp (ref "R201")
      (value "200k")
      (footprint "eagle-import:R0805")
      (libsource (lib "eagle-import") (part "R-EU_R0805"))
    )
    (comp (ref "R202")
      (value "200k")
      (footprint "eagle-import:R0805")
      (libsource (lib "eagle-import") (part "R-EU_R0805"))
    )
    (comp (ref "R203")
      (value "200k")
      (footprint "eagle-import:R0805")
      (libsource (lib "eagle-import") (part "R-EU_R0805"))
    )
    (comp (ref "R204")
      (value "200k")
      (footprint "eagle-import:R0805")
      (libsource (lib "eagle-import") (part "R-EU_R0805"))
    )
    (comp (ref "R205")
      (value "200k")
      (footprint "eagle-import:R0805")
      (libsource (lib "eagle-import") (part "R-EU_R0805"))
    )
    (comp (ref "R206")
      (value "200k")
      (footprint "eagle-import:R0805")
      (libsource (lib "eagle-import") (part "R-EU_R0805"))
    )
    (comp (ref "R207")
      (value "10k")
      (footprint "eagle-import:R0805")
      (libsource (lib "eagle-import") (part "R-EU_R0805"))
    )
    (comp (ref "X1")
      (value "MKDSN1,5/2-5,08")
      (footprint "eagle-import:MKDSN1,5_2-5,08")
      (libsource (lib "eagle-import") (part "MKDSN1,5/2-5,08"))
    )
    (comp (ref "X2")
      (value "MKDSN1,5/2-5,08")
      (footprint "eagle-import:MKDSN1,5_2-5,08")
      (libsource (lib "eagle-import") (part "MKDSN1,5/2-5,08"))
    )
    (comp (ref "X5")
      (value "MKDSN1,5/2-5,08")
      (footprint "eagle-import:MKDSN1,5_2-5,08")
      (libsource (lib "eagle-import") (part "MKDSN1,5/2-5,08"))
    )
    (comp (ref "X6")
      (value "MKDSN1,5/2-5,08")
      (footprint "eagle-import:MKDSN1,5_2-5,08")
      (libsource (lib "eagle-import") (part "MKDSN1,5/2-5,08"))
    )
    (comp (ref "X7")
      (value "MKDSN1,5/2-5,08")
      (footprint "eagle-import:MKDSN1,5_2-5,08")
      (libsource (lib "eagle-import") (part "MKDSN1,5/2-5,08"))
    )
    (comp (ref "X8")
      (value "MKDSN1,5/2-5,08")
      (footprint "eagle-import:MKDSN1,5_2-5,08")
      (libsource (lib "eagle-import") (part "MKDSN1,5/2-5,08"))
    )
    (comp (ref "X9")
      (value "MKDSN1,5/2-5,08")
      (footprint "eagle-import:MKDSN1,5_2-5,08")
      (libsource (lib "eagle-import") (part "MKDSN1,5/2-5,08"))
    )
    (comp (ref "X10")
      (value "MKDSN1,5/2-5,08")
      (footprint "eagle-import:MKDSN1,5_2-5,08")
      (libsource (lib "eagle-import") (part "MKDSN1,5/2-5,08"))
    )
    (comp (ref "X11")
      (value "MKDSN1,5/2-5,08")
      (footprint "eagle-import:MKDSN1,5_2-5,08")
      (libsource (lib "eagle-import") (part "MKDSN1,5/2-5,08"))
    )
    (comp (ref "X12")
      (value "MKDSN1,5/2-5,08")
      (footprint "eagle-import:MKDSN1,5_2-5,08")
      (libsource (lib "eagle-import") (part "MKDSN1,5/2-5,08"))
    )
    (comp (ref "X13")
      (value "MKDSN1,5/2-5,08")
      (footprint "eagle-import:MKDSN1,5_2-5,08")
      (libsource (lib "eagle-import") (part "MKDSN1,5/2-5,08"))
    )
    (comp (ref "X14")
      (value "MKDSN1,5/2-5,08")
      (footprint "eagle-import:MKDSN1,5_2-5,08")
      (libsource (lib "eagle-import") (part "MKDSN1,5/2-5,08"))
    )
    (comp (ref "X15")
      (value "MKDSN1,5/2-5,08")
      (footprint "eagle-import:MKDSN1,5_2-5,08")
      (libsource (lib "eagle-import") (part "MKDSN1,5/2-5,08"))
    )
    (comp (ref "X16")
      (value "MKDSN1,5/2-5,08")
      (footprint "eagle-import:MKDSN1,5_2-5,08")
      (libsource (lib "eagle-import") (part "MKDSN1,5/2-5,08"))
    )
    (comp (ref "X17")
      (value "MKDSN1,5/2-5,08")
      (footprint "eagle-import:MKDSN1,5_2-5,08")
      (libsource (lib "eagle-import") (part "MKDSN1,5/2-5,08"))
    )
    (comp (ref "X18")
      (value "MKDSN1,5/2-5,08")
      (footprint "eagle-import:MKDSN1,5_2-5,08")
      (libsource (lib "eagle-import") (part "MKDSN1,5/2-5,08"))
    )
  )
  (nets
    (net (code "1") (name "5VDC") (class "Default")
      (node (ref "C1") (pin "2") (pinfunction "2_2") (pintype "passive"))
      (node (ref "C11") (pin "2") (pinfunction "2_2") (pintype "passive"))
      (node (ref "C13") (pin "2") (pinfunction "2_2") (pintype "passive"))
      (node (ref "C15") (pin "2") (pinfunction "2_2") (pintype "passive"))
      (node (ref "C17") (pin "2") (pinfunction "2_2") (pintype "passive"))
      (node (ref "C5") (pin "2") (pinfunction "2_2") (pintype "passive"))
      (node (ref "C7") (pin "2") (pinfunction "2_2") (pintype "passive"))
      (node (ref "C9") (pin "2") (pinfunction "2_2") (pintype "passive"))
      (node (ref "JP1") (pin "1") (pinfunction "1_1") (pintype "passive"))
      (node (ref "JP1") (pin "2") (pinfunction "2_2") (pintype "passive"))
      (node (ref "JP10") (pin "1") (pinfunction "1_1") (pintype "passive"))
      (node (ref "JP10") (pin "2") (pinfunction "2_2") (pintype "passive"))
      (node (ref "JP13") (pin "1") (pinfunction "1_1") (pintype "passive"))
      (node (ref "JP13") (pin "2") (pinfunction "2_2") (pintype "passive"))
      (node (ref "JP16") (pin "1") (pinfunction "1_1") (pintype "passive"))
      (node (ref "JP16") (pin "2") (pinfunction "2_2") (pintype "passive"))
      (node (ref "JP19") (pin "1") (pinfunction "1_1") (pintype "passive"))
      (node (ref "JP19") (pin "2") (pinfunction "2_2") (pintype "passive"))
      (node (ref "JP22") (pin "1") (pinfunction "1_1") (pintype "passive"))
      (node (ref "JP22") (pin "2") (pinfunction "2_2") (pintype "passive"))
      (node (ref "JP25") (pin "1") (pinfunction "1_1") (pintype "passive"))
      (node (ref "JP25") (pin "2") (pinfunction "2_2") (pintype "passive"))
      (node (ref "JP7") (pin "1") (pinfunction "1_1") (pintype "passive"))
      (node (ref "JP7") (pin "2") (pinfunction "2_2") (pintype "passive"))
      (node (ref "R1") (pin "1") (pinfunction "1_1") (pintype "passive"))
      (node (ref "R116") (pin "1") (pinfunction "1_1") (pintype "passive"))
      (node (ref "R139") (pin "1") (pinfunction "1_1") (pintype "passive"))
      (node (ref "R162") (pin "1") (pinfunction "1_1") (pintype "passive"))
      (node (ref "R185") (pin "1") (pinfunction "1_1") (pintype "passive"))
      (node (ref "R46") (pin "1") (pinfunction "1_1") (pintype "passive"))
      (node (ref "R70") (pin "1") (pinfunction "1_1") (pintype "passive"))
      (node (ref "R93") (pin "1") (pinfunction "1_1") (pintype "passive"))
    )
    (net (code "2") (name "GND") (class "Default")
      (node (ref "C1") (pin "1") (pinfunction "1_1") (pintype "passive"))
      (node (ref "C10") (pin "1") (pinfunction "1_1") (pintype "passive"))
      (node (ref "C11") (pin "1") (pinfunction "1_1") (pintype "passive"))
      (node (ref "C12") (pin "1") (pinfunction "1_1") (pintype "passive"))
      (node (ref "C13") (pin "1") (pinfunction "1_1") (pintype "passive"))
      (node (ref "C14") (pin "1") (pinfunction "1_1") (pintype "passive"))
      (node (ref "C15") (pin "1") (pinfunction "1_1") (pintype "passive"))
      (node (ref "C16") (pin "1") (pinfunction "1_1") (pintype "passive"))
      (node (ref "C17") (pin "1") (pinfunction "1_1") (pintype "passive"))
      (node (ref "C18") (pin "1") (pinfunction "1_1") (pintype "passive"))
      (node (ref "C2") (pin "1") (pinfunction "1_1") (pintype "passive"))
      (node (ref "C5") (pin "1") (pinfunction "1_1") (pintype "passive"))
      (node (ref "C6") (pin "1") (pinfunction "1_1") (pintype "passive"))
      (node (ref "C7") (pin "1") (pinfunction "1_1") (pintype "passive"))
      (node (ref "C8") (pin "1") (pinfunction "1_1") (pintype "passive"))
      (node (ref "C9") (pin "1") (pinfunction "1_1") (pintype "passive"))
      (node (ref "JP1") (pin "4") (pinfunction "4_4") (pintype "passive"))
      (node (ref "JP1") (pin "5") (pinfunction "5_5") (pintype "passive"))
      (node (ref "JP10") (pin "4") (pinfunction "4_4") (pintype "passive"))
      (node (ref "JP10") (pin "5") (pinfunction "5_5") (pintype "passive"))
      (node (ref "JP11") (pin "1") (pinfunction "1_1") (pintype "passive"))
      (node (ref "JP11") (pin "2") (pinfunction "2_2") (pintype "passive"))
      (node (ref "JP12") (pin "1") (pinfunction "1_1") (pintype "passive"))
      (node (ref "JP12") (pin "2") (pinfunction "2_2") (pintype "passive"))
      (node (ref "JP13") (pin "4") (pinfunction "4_4") (pintype "passive"))
      (node (ref "JP13") (pin "5") (pinfunction "5_5") (pintype "passive"))
      (node (ref "JP14") (pin "1") (pinfunction "1_1") (pintype "passive"))
      (node (ref "JP14") (pin "2") (pinfunction "2_2") (pintype "passive"))
      (node (ref "JP15") (pin "1") (pinfunction "1_1") (pintype "passive"))
      (node (ref "JP15") (pin "2") (pinfunction "2_2") (pintype "passive"))
      (node (ref "JP16") (pin "4") (pinfunction "4_4") (pintype "passive"))
      (node (ref "JP16") (pin "5") (pinfunction "5_5") (pintype "passive"))
      (node (ref "JP17") (pin "1") (pinfunction "1_1") (pintype "passive"))
      (node (ref "JP17") (pin "2") (pinfunction "2_2") (pintype "passive"))
      (node (ref "JP18") (pin "1") (pinfunction "1_1") (pintype "passive"))
      (node (ref "JP18") (pin "2") (pinfunction "2_2") (pintype "passive"))
      (node (ref "JP19") (pin "4") (pinfunction "4_4") (pintype "passive"))
      (node (ref "JP19") (pin "5") (pinfunction "5_5") (pintype "passive"))
      (node (ref "JP2") (pin "1") (pinfunction "1_1") (pintype "passive"))
      (node (ref "JP2") (pin "2") (pinfunction "2_2") (pintype "passive"))
      (node (ref "JP20") (pin "1") (pinfunction "1_1") (pintype "passive"))
      (node (ref "JP20") (pin "2") (pinfunction "2_2") (pintype "passive"))
      (node (ref "JP21") (pin "1") (pinfunction "1_1") (pintype "passive"))
      (node (ref "JP21") (pin "2") (pinfunction "2_2") (pintype "passive"))
      (node (ref "JP22") (pin "4") (pinfunction "4_4") (pintype "passive"))
      (node (ref "JP22") (pin "5") (pinfunction "5_5") (pintype "passive"))
      (node (ref "JP23") (pin "1") (pinfunction "1_1") (pintype "passive"))
      (node (ref "JP23") (pin "2") (pinfunction "2_2") (pintype "passive"))
      (node (ref "JP24") (pin "1") (pinfunction "1_1") (pintype "passive"))
      (node (ref "JP24") (pin "2") (pinfunction "2_2") (pintype "passive"))
      (node (ref "JP25") (pin "4") (pinfunction "4_4") (pintype "passive"))
      (node (ref "JP25") (pin "5") (pinfunction "5_5") (pintype "passive"))
      (node (ref "JP26") (pin "1") (pinfunction "1_1") (pintype "passive"))
      (node (ref "JP26") (pin "2") (pinfunction "2_2") (pintype "passive"))
      (node (ref "JP27") (pin "1") (pinfunction "1_1") (pintype "passive"))
      (node (ref "JP27") (pin "2") (pinfunction "2_2") (pintype "passive"))
      (node (ref "JP3") (pin "1") (pinfunction "1_1") (pintype "passive"))
      (node (ref "JP3") (pin "2") (pinfunction "2_2") (pintype "passive"))
      (node (ref "JP7") (pin "4") (pinfunction "4_4") (pintype "passive"))
      (node (ref "JP7") (pin "5") (pinfunction "5_5") (pintype "passive"))
      (node (ref "JP8") (pin "1") (pinfunction "1_1") (pintype "passive"))
      (node (ref "JP8") (pin "2") (pinfunction "2_2") (pintype "passive"))
      (node (ref "JP9") (pin "1") (pinfunction "1_1") (pintype "passive"))
      (node (ref "JP9") (pin "2") (pinfunction "2_2") (pintype "passive"))
      (node (ref "LED1") (pin "C") (pinfunction "C_C") (pintype "passive"))
      (node (ref "LED3") (pin "C") (pinfunction "C_C") (pintype "passive"))
      (node (ref "LED4") (pin "C") (pinfunction "C_C") (pintype "passive"))
      (node (ref "LED5") (pin "C") (pinfunction "C_C") (pintype "passive"))
      (node (ref "LED6") (pin "C") (pinfunction "C_C") (pintype "passive"))
      (node (ref "LED7") (pin "C") (pinfunction "C_C") (pintype "passive"))
      (node (ref "LED8") (pin "C") (pinfunction "C_C") (pintype "passive"))
      (node (ref "LED9") (pin "C") (pinfunction "C_C") (pintype "passive"))
      (node (ref "R104") (pin "1") (pinfunction "1_1") (pintype "passive"))
      (node (ref "R115") (pin "1") (pinfunction "1_1") (pintype "passive"))
      (node (ref "R127") (pin "1") (pinfunction "1_1") (pintype "passive"))
      (node (ref "R138") (pin "1") (pinfunction "1_1") (pintype "passive"))
      (node (ref "R15") (pin "1") (pinfunction "1_1") (pintype "passive"))
      (node (ref "R150") (pin "1") (pinfunction "1_1") (pintype "passive"))
      (node (ref "R161") (pin "1") (pinfunction "1_1") (pintype "passive"))
      (node (ref "R173") (pin "1") (pinfunction "1_1") (pintype "passive"))
      (node (ref "R184") (pin "1") (pinfunction "1_1") (pintype "passive"))
      (node (ref "R196") (pin "1") (pinfunction "1_1") (pintype "passive"))
      (node (ref "R207") (pin "1") (pinfunction "1_1") (pintype "passive"))
      (node (ref "R53") (pin "1") (pinfunction "1_1") (pintype "passive"))
      (node (ref "R58") (pin "1") (pinfunction "1_1") (pintype "passive"))
      (node (ref "R69") (pin "1") (pinfunction "1_1") (pintype "passive"))
      (node (ref "R81") (pin "1") (pinfunction "1_1") (pintype "passive"))
      (node (ref "R92") (pin "1") (pinfunction "1_1") (pintype "passive"))
      (node (ref "X10") (pin "1") (pinfunction "KL_1") (pintype "passive"))
      (node (ref "X12") (pin "1") (pinfunction "KL_1") (pintype "passive"))
      (node (ref "X14") (pin "1") (pinfunction "KL_1") (pintype "passive"))
      (node (ref "X16") (pin "1") (pinfunction "KL_1") (pintype "passive"))
      (node (ref "X18") (pin "1") (pinfunction "KL_1") (pintype "passive"))
      (node (ref "X2") (pin "1") (pinfunction "KL_1") (pintype "passive"))
      (node (ref "X6") (pin "1") (pinfunction "KL_1") (pintype "passive"))
      (node (ref "X8") (pin "1") (pinfunction "KL_1") (pintype "passive"))
    )
    (net (code "3") (name "HV+") (class "Default")
      (node (ref "R105") (pin "1") (pinfunction "1_1") (pintype "passive"))
      (node (ref "R117") (pin "1") (pinfunction "1_1") (pintype "passive"))
      (node (ref "R128") (pin "1") (pinfunction "1_1") (pintype "passive"))
      (node (ref "R140") (pin "1") (pinfunction "1_1") (pintype "passive"))
      (node (ref "R151") (pin "1") (pinfunction "1_1") (pintype "passive"))
      (node (ref "R163") (pin "1") (pinfunction "1_1") (pintype "passive"))
      (node (ref "R174") (pin "1") (pinfunction "1_1") (pintype "passive"))
      (node (ref "R186") (pin "1") (pinfunction "1_1") (pintype "passive"))
      (node (ref "R197") (pin "1") (pinfunction "1_1") (pintype "passive"))
      (node (ref "R2") (pin "1") (pinfunction "1_1") (pintype "passive"))
      (node (ref "R3") (pin "1") (pinfunction "1_1") (pintype "passive"))
      (node (ref "R47") (pin "1") (pinfunction "1_1") (pintype "passive"))
      (node (ref "R59") (pin "1") (pinfunction "1_1") (pintype "passive"))
      (node (ref "R71") (pin "1") (pinfunction "1_1") (pintype "passive"))
      (node (ref "R82") (pin "1") (pinfunction "1_1") (pintype "passive"))
      (node (ref "R94") (pin "1") (pinfunction "1_1") (pintype "passive"))
      (node (ref "X1") (pin "2") (pinfunction "KL_2") (pintype "passive"))
      (node (ref "X11") (pin "2") (pinfunction "KL_2") (pintype "passive"))
      (node (ref "X13") (pin "2") (pinfunction "KL_2") (pintype "passive"))
      (node (ref "X15") (pin "2") (pinfunction "KL_2") (pintype "passive"))
      (node (ref "X17") (pin "2") (pinfunction "KL_2") (pintype "passive"))
      (node (ref "X5") (pin "2") (pinfunction "KL_2") (pintype "passive"))
      (node (ref "X7") (pin "2") (pinfunction "KL_2") (pintype "passive"))
      (node (ref "X9") (pin "2") (pinfunction "KL_2") (pintype "passive"))
    )
    (net (code "4") (name "Net-(C2-Pad2)") (class "Default")
      (node (ref "C2") (pin "2") (pinfunction "2_2") (pintype "passive"))
      (node (ref "JP1") (pin "3") (pinfunction "3_3") (pintype "passive"))
      (node (ref "R14") (pin "2") (pinfunction "2_2") (pintype "passive"))
      (node (ref "R15") (pin "2") (pinfunction "2_2") (pintype "passive"))
      (node (ref "R45") (pin "2") (pinfunction "2_2") (pintype "passive"))
      (node (ref "R53") (pin "2") (pinfunction "2_2") (pintype "passive"))
    )
    (net (code "5") (name "Net-(C6-Pad2)") (class "Default")
      (node (ref "C6") (pin "2") (pinfunction "2_2") (pintype "passive"))
      (node (ref "JP7") (pin "3") (pinfunction "3_3") (pintype "passive"))
      (node (ref "R57") (pin "2") (pinfunction "2_2") (pintype "passive"))
      (node (ref "R58") (pin "2") (pinfunction "2_2") (pintype "passive"))
      (node (ref "R68") (pin "2") (pinfunction "2_2") (pintype "passive"))
      (node (ref "R69") (pin "2") (pinfunction "2_2") (pintype "passive"))
    )
    (net (code "6") (name "Net-(C8-Pad2)") (class "Default")
      (node (ref "C8") (pin "2") (pinfunction "2_2") (pintype "passive"))
      (node (ref "JP10") (pin "3") (pinfunction "3_3") (pintype "passive"))
      (node (ref "R80") (pin "2") (pinfunction "2_2") (pintype "passive"))
      (node (ref "R81") (pin "2") (pinfunction "2_2") (pintype "passive"))
      (node (ref "R91") (pin "2") (pinfunction "2_2") (pintype "passive"))
      (node (ref "R92") (pin "2") (pinfunction "2_2") (pintype "passive"))
    )
    (net (code "7") (name "Net-(C10-Pad2)") (class "Default")
      (node (ref "C10") (pin "2") (pinfunction "2_2") (pintype "passive"))
      (node (ref "JP13") (pin "3") (pinfunction "3_3") (pintype "passive"))
      (node (ref "R103") (pin "2") (pinfunction "2_2") (pintype "passive"))
      (node (ref "R104") (pin "2") (pinfunction "2_2") (pintype "passive"))
      (node (ref "R114") (pin "2") (pinfunction "2_2") (pintype "passive"))
      (node (ref "R115") (pin "2") (pinfunction "2_2") (pintype "passive"))
    )
    (net (code "8") (name "Net-(C12-Pad2)") (class "Default")
      (node (ref "C12") (pin "2") (pinfunction "2_2") (pintype "passive"))
      (node (ref "JP16") (pin "3") (pinfunction "3_3") (pintype "passive"))
      (node (ref "R126") (pin "2") (pinfunction "2_2") (pintype "passive"))
      (node (ref "R127") (pin "2") (pinfunction "2_2") (pintype "passive"))
      (node (ref "R137") (pin "2") (pinfunction "2_2") (pintype "passive"))
      (node (ref "R138") (pin "2") (pinfunction "2_2") (pintype "passive"))
    )
    (net (code "9") (name "Net-(C14-Pad2)") (class "Default")
      (node (ref "C14") (pin "2") (pinfunction "2_2") (pintype "passive"))
      (node (ref "JP19") (pin "3") (pinfunction "3_3") (pintype "passive"))
      (node (ref "R149") (pin "2") (pinfunction "2_2") (pintype "passive"))
      (node (ref "R150") (pin "2") (pinfunction "2_2") (pintype "passive"))
      (node (ref "R160") (pin "2") (pinfunction "2_2") (pintype "passive"))
      (node (ref "R161") (pin "2") (pinfunction "2_2") (pintype "passive"))
    )
    (net (code "10") (name "Net-(C16-Pad2)") (class "Default")
      (node (ref "C16") (pin "2") (pinfunction "2_2") (pintype "passive"))
      (node (ref "JP22") (pin "3") (pinfunction "3_3") (pintype "passive"))
      (node (ref "R172") (pin "2") (pinfunction "2_2") (pintype "passive"))
      (node (ref "R173") (pin "2") (pinfunction "2_2") (pintype "passive"))
      (node (ref "R183") (pin "2") (pinfunction "2_2") (pintype "passive"))
      (node (ref "R184") (pin "2") (pinfunction "2_2") (pintype "passive"))
    )
    (net (code "11") (name "Net-(C18-Pad2)") (class "Default")
      (node (ref "C18") (pin "2") (pinfunction "2_2") (pintype "passive"))
      (node (ref "JP25") (pin "3") (pinfunction "3_3") (pintype "passive"))
      (node (ref "R195") (pin "2") (pinfunction "2_2") (pintype "passive"))
      (node (ref "R196") (pin "2") (pinfunction "2_2") (pintype "passive"))
      (node (ref "R206") (pin "2") (pinfunction "2_2") (pintype "passive"))
      (node (ref "R207") (pin "2") (pinfunction "2_2") (pintype "passive"))
    )
    (net (code "12") (name "Net-(LED1-PadA)") (class "Default")
      (node (ref "LED1") (pin "A") (pinfunction "A_A") (pintype "passive"))
      (node (ref "R1") (pin "2") (pinfunction "2_2") (pintype "passive"))
    )
    (net (code "13") (name "Net-(LED3-PadA)") (class "Default")
      (node (ref "LED3") (pin "A") (pinfunction "A_A") (pintype "passive"))
      (node (ref "R46") (pin "2") (pinfunction "2_2") (pintype "passive"))
    )
    (net (code "14") (name "Net-(LED4-PadA)") (class "Default")
      (node (ref "LED4") (pin "A") (pinfunction "A_A") (pintype "passive"))
      (node (ref "R70") (pin "2") (pinfunction "2_2") (pintype "passive"))
    )
    (net (code "15") (name "Net-(LED5-PadA)") (class "Default")
      (node (ref "LED5") (pin "A") (pinfunction "A_A") (pintype "passive"))
      (node (ref "R93") (pin "2") (pinfunction "2_2") (pintype "passive"))
    )
    (net (code "16") (name "Net-(LED6-PadA)") (class "Default")
      (node (ref "LED6") (pin "A") (pinfunction "A_A") (pintype "passive"))
      (node (ref "R116") (pin "2") (pinfunction "2_2") (pintype "passive"))
    )
    (net (code "17") (name "Net-(LED7-PadA)") (class "Default")
      (node (ref "LED7") (pin "A") (pinfunction "A_A") (pintype "passive"))
      (node (ref "R139") (pin "2") (pinfunction "2_2") (pintype "passive"))
    )
    (net (code "18") (name "Net-(LED8-PadA)") (class "Default")
      (node (ref "LED8") (pin "A") (pinfunction "A_A") (pintype "passive"))
      (node (ref "R162") (pin "2") (pinfunction "2_2") (pintype "passive"))
    )
    (net (code "19") (name "Net-(LED9-PadA)") (class "Default")
      (node (ref "LED9") (pin "A") (pinfunction "A_A") (pintype "passive"))
      (node (ref "R185") (pin "2") (pinfunction "2_2") (pintype "passive"))
    )
    (net (code "20") (name "Net-(R2-Pad2)") (class "Default")
      (node (ref "R2") (pin "2") (pinfunction "2_2") (pintype "passive"))
      (node (ref "R4") (pin "1") (pinfunction "1_1") (pintype "passive"))
    )
    (net (code "21") (name "Net-(R3-Pad2)") (class "Default")
      (node (ref "R3") (pin "2") (pinfunction "2_2") (pintype "passive"))
      (node (ref "R8") (pin "1") (pinfunction "1_1") (pintype "passive"))
    )
    (net (code "22") (name "Net-(R4-Pad2)") (class "Default")
      (node (ref "R4") (pin "2") (pinfunction "2_2") (pintype "passive"))
      (node (ref "R5") (pin "1") (pinfunction "1_1") (pintype "passive"))
    )
    (net (code "23") (name "Net-(R5-Pad2)") (class "Default")
      (node (ref "R5") (pin "2") (pinfunction "2_2") (pintype "passive"))
      (node (ref "R6") (pin "1") (pinfunction "1_1") (pintype "passive"))
    )
    (net (code "24") (name "Net-(R6-Pad2)") (class "Default")
      (node (ref "R6") (pin "2") (pinfunction "2_2") (pintype "passive"))
      (node (ref "R7") (pin "1") (pinfunction "1_1") (pintype "passive"))
    )
    (net (code "25") (name "Net-(R7-Pad2)") (class "Default")
      (node (ref "R7") (pin "2") (pinfunction "2_2") (pintype "passive"))
      (node (ref "R9") (pin "1") (pinfunction "1_1") (pintype "passive"))
    )
    (net (code "26") (name "Net-(R10-Pad1)") (class "Default")
      (node (ref "R10") (pin "1") (pinfunction "1_1") (pintype "passive"))
      (node (ref "R9") (pin "2") (pinfunction "2_2") (pintype "passive"))
    )
    (net (code "27") (name "Net-(R10-Pad2)") (class "Default")
      (node (ref "R10") (pin "2") (pinfunction "2_2") (pintype "passive"))
      (node (ref "R11") (pin "1") (pinfunction "1_1") (pintype "passive"))
    )
    (net (code "28") (name "Net-(R11-Pad2)") (class "Default")
      (node (ref "R11") (pin "2") (pinfunction "2_2") (pintype "passive"))
      (node (ref "R12") (pin "1") (pinfunction "1_1") (pintype "passive"))
    )
    (net (code "29") (name "Net-(R12-Pad2)") (class "Default")
      (node (ref "R12") (pin "2") (pinfunction "2_2") (pintype "passive"))
      (node (ref "R14") (pin "1") (pinfunction "1_1") (pintype "passive"))
    )
    (net (code "30") (name "Net-(R13-Pad1)") (class "Default")
      (node (ref "R13") (pin "1") (pinfunction "1_1") (pintype "passive"))
      (node (ref "R8") (pin "2") (pinfunction "2_2") (pintype "passive"))
    )
    (net (code "31") (name "Net-(R13-Pad2)") (class "Default")
      (node (ref "R13") (pin "2") (pinfunction "2_2") (pintype "passive"))
      (node (ref "R18") (pin "1") (pinfunction "1_1") (pintype "passive"))
    )
    (net (code "32") (name "Net-(R18-Pad2)") (class "Default")
      (node (ref "R18") (pin "2") (pinfunction "2_2") (pintype "passive"))
      (node (ref "R23") (pin "1") (pinfunction "1_1") (pintype "passive"))
    )
    (net (code "33") (name "Net-(R23-Pad2)") (class "Default")
      (node (ref "R23") (pin "2") (pinfunction "2_2") (pintype "passive"))
      (node (ref "R28") (pin "1") (pinfunction "1_1") (pintype "passive"))
    )
    (net (code "34") (name "Net-(R28-Pad2)") (class "Default")
      (node (ref "R28") (pin "2") (pinfunction "2_2") (pintype "passive"))
      (node (ref "R33") (pin "1") (pinfunction "1_1") (pintype "passive"))
    )
    (net (code "35") (name "Net-(R33-Pad2)") (class "Default")
      (node (ref "R33") (pin "2") (pinfunction "2_2") (pintype "passive"))
      (node (ref "R38") (pin "1") (pinfunction "1_1") (pintype "passive"))
    )
    (net (code "36") (name "Net-(R38-Pad2)") (class "Default")
      (node (ref "R38") (pin "2") (pinfunction "2_2") (pintype "passive"))
      (node (ref "R43") (pin "1") (pinfunction "1_1") (pintype "passive"))
    )
    (net (code "37") (name "Net-(R43-Pad2)") (class "Default")
      (node (ref "R43") (pin "2") (pinfunction "2_2") (pintype "passive"))
      (node (ref "R45") (pin "1") (pinfunction "1_1") (pintype "passive"))
    )
    (net (code "38") (name "Net-(R47-Pad2)") (class "Default")
      (node (ref "R47") (pin "2") (pinfunction "2_2") (pintype "passive"))
      (node (ref "R48") (pin "1") (pinfunction "1_1") (pintype "passive"))
    )
    (net (code "39") (name "Net-(R48-Pad2)") (class "Default")
      (node (ref "R48") (pin "2") (pinfunction "2_2") (pintype "passive"))
      (node (ref "R49") (pin "1") (pinfunction "1_1") (pintype "passive"))
    )
    (net (code "40") (name "Net-(R49-Pad2)") (class "Default")
      (node (ref "R49") (pin "2") (pinfunction "2_2") (pintype "passive"))
      (node (ref "R50") (pin "1") (pinfunction "1_1") (pintype "passive"))
    )
    (net (code "41") (name "Net-(R50-Pad2)") (class "Default")
      (node (ref "R50") (pin "2") (pinfunction "2_2") (pintype "passive"))
      (node (ref "R51") (pin "1") (pinfunction "1_1") (pintype "passive"))
    )
    (net (code "42") (name "Net-(R51-Pad2)") (class "Default")
      (node (ref "R51") (pin "2") (pinfunction "2_2") (pintype "passive"))
      (node (ref "R52") (pin "1") (pinfunction "1_1") (pintype "passive"))
    )
    (net (code "43") (name "Net-(R52-Pad2)") (class "Default")
      (node (ref "R52") (pin "2") (pinfunction "2_2") (pintype "passive"))
      (node (ref "R54") (pin "1") (pinfunction "1_1") (pintype "passive"))
    )
    (net (code "44") (name "Net-(R54-Pad2)") (class "Default")
      (node (ref "R54") (pin "2") (pinfunction "2_2") (pintype "passive"))
      (node (ref "R55") (pin "1") (pinfunction "1_1") (pintype "passive"))
    )
    (net (code "45") (name "Net-(R55-Pad2)") (class "Default")
      (node (ref "R55") (pin "2") (pinfunction "2_2") (pintype "passive"))
      (node (ref "R56") (pin "1") (pinfunction "1_1") (pintype "passive"))
    )
    (net (code "46") (name "Net-(R56-Pad2)") (class "Default")
      (node (ref "R56") (pin "2") (pinfunction "2_2") (pintype "passive"))
      (node (ref "R57") (pin "1") (pinfunction "1_1") (pintype "passive"))
    )
    (net (code "47") (name "Net-(R59-Pad2)") (class "Default")
      (node (ref "R59") (pin "2") (pinfunction "2_2") (pintype "passive"))
      (node (ref "R60") (pin "1") (pinfunction "1_1") (pintype "passive"))
    )
    (net (code "48") (name "Net-(R60-Pad2)") (class "Default")
      (node (ref "R60") (pin "2") (pinfunction "2_2") (pintype "passive"))
      (node (ref "R61") (pin "1") (pinfunction "1_1") (pintype "passive"))
    )
    (net (code "49") (name "Net-(R61-Pad2)") (class "Default")
      (node (ref "R61") (pin "2") (pinfunction "2_2") (pintype "passive"))
      (node (ref "R62") (pin "1") (pinfunction "1_1") (pintype "passive"))
    )
    (net (code "50") (name "Net-(R62-Pad2)") (class "Default")
      (node (ref "R62") (pin "2") (pinfunction "2_2") (pintype "passive"))
      (node (ref "R63") (pin "1") (pinfunction "1_1") (pintype "passive"))
    )
    (net (code "51") (name "Net-(R63-Pad2)") (class "Default")
      (node (ref "R63") (pin "2") (pinfunction "2_2") (pintype "passive"))
      (node (ref "R64") (pin "1") (pinfunction "1_1") (pintype "passive"))
    )
    (net (code "52") (name "Net-(R64-Pad2)") (class "Default")
      (node (ref "R64") (pin "2") (pinfunction "2_2") (pintype "passive"))
      (node (ref "R65") (pin "1") (pinfunction "1_1") (pintype "passive"))
    )
    (net (code "53") (name "Net-(R65-Pad2)") (class "Default")
      (node (ref "R65") (pin "2") (pinfunction "2_2") (pintype "passive"))
      (node (ref "R66") (pin "1") (pinfunction "1_1") (pintype "passive"))
    )
    (net (code "54") (name "Net-(R66-Pad2)") (class "Default")
      (node (ref "R66") (pin "2") (pinfunction "2_2") (pintype "passive"))
      (node (ref "R67") (pin "1") (pinfunction "1_1") (pintype "passive"))
    )
    (net (code "55") (name "Net-(R67-Pad2)") (class "Default")
      (node (ref "R67") (pin "2") (pinfunction "2_2") (pintype "passive"))
      (node (ref "R68") (pin "1") (pinfunction "1_1") (pintype "passive"))
    )
    (net (code "56") (name "Net-(R71-Pad2)") (class "Default")
      (node (ref "R71") (pin "2") (pinfunction "2_2") (pintype "passive"))
      (node (ref "R72") (pin "1") (pinfunction "1_1") (pintype "passive"))
    )
    (net (code "57") (name "Net-(R72-Pad2)") (class "Default")
      (node (ref "R72") (pin "2") (pinfunction "2_2") (pintype "passive"))
      (node (ref "R73") (pin "1") (pinfunction "1_1") (pintype "passive"))
    )
    (net (code "58") (name "Net-(R73-Pad2)") (class "Default")
      (node (ref "R73") (pin "2") (pinfunction "2_2") (pintype "passive"))
      (node (ref "R74") (pin "1") (pinfunction "1_1") (pintype "passive"))
    )
    (net (code "59") (name "Net-(R74-Pad2)") (class "Default")
      (node (ref "R74") (pin "2") (pinfunction "2_2") (pintype "passive"))
      (node (ref "R75") (pin "1") (pinfunction "1_1") (pintype "passive"))
    )
    (net (code "60") (name "Net-(R75-Pad2)") (class "Default")
      (node (ref "R75") (pin "2") (pinfunction "2_2") (pintype "passive"))
      (node (ref "R76") (pin "1") (pinfunction "1_1") (pintype "passive"))
    )
    (net (code "61") (name "Net-(R76-Pad2)") (class "Default")
      (node (ref "R76") (pin "2") (pinfunction "2_2") (pintype "passive"))
      (node (ref "R77") (pin "1") (pinfunction "1_1") (pintype "passive"))
    )
    (net (code "62") (name "Net-(R77-Pad2)") (class "Default")
      (node (ref "R77") (pin "2") (pinfunction "2_2") (pintype "passive"))
      (node (ref "R78") (pin "1") (pinfunction "1_1") (pintype "passive"))
    )
    (net (code "63") (name "Net-(R78-Pad2)") (class "Default")
      (node (ref "R78") (pin "2") (pinfunction "2_2") (pintype "passive"))
      (node (ref "R79") (pin "1") (pinfunction "1_1") (pintype "passive"))
    )
    (net (code "64") (name "Net-(R79-Pad2)") (class "Default")
      (node (ref "R79") (pin "2") (pinfunction "2_2") (pintype "passive"))
      (node (ref "R80") (pin "1") (pinfunction "1_1") (pintype "passive"))
    )
    (net (code "65") (name "Net-(R82-Pad2)") (class "Default")
      (node (ref "R82") (pin "2") (pinfunction "2_2") (pintype "passive"))
      (node (ref "R83") (pin "1") (pinfunction "1_1") (pintype "passive"))
    )
    (net (code "66") (name "Net-(R83-Pad2)") (class "Default")
      (node (ref "R83") (pin "2") (pinfunction "2_2") (pintype "passive"))
      (node (ref "R84") (pin "1") (pinfunction "1_1") (pintype "passive"))
    )
    (net (code "67") (name "Net-(R84-Pad2)") (class "Default")
      (node (ref "R84") (pin "2") (pinfunction "2_2") (pintype "passive"))
      (node (ref "R85") (pin "1") (pinfunction "1_1") (pintype "passive"))
    )
    (net (code "68") (name "Net-(R85-Pad2)") (class "Default")
      (node (ref "R85") (pin "2") (pinfunction "2_2") (pintype "passive"))
      (node (ref "R86") (pin "1") (pinfunction "1_1") (pintype "passive"))
    )
    (net (code "69") (name "Net-(R86-Pad2)") (class "Default")
      (node (ref "R86") (pin "2") (pinfunction "2_2") (pintype "passive"))
      (node (ref "R87") (pin "1") (pinfunction "1_1") (pintype "passive"))
    )
    (net (code "70") (name "Net-(R87-Pad2)") (class "Default")
      (node (ref "R87") (pin "2") (pinfunction "2_2") (pintype "passive"))
      (node (ref "R88") (pin "1") (pinfunction "1_1") (pintype "passive"))
    )
    (net (code "71") (name "Net-(R88-Pad2)") (class "Default")
      (node (ref "R88") (pin "2") (pinfunction "2_2") (pintype "passive"))
      (node (ref "R89") (pin "1") (pinfunction "1_1") (pintype "passive"))
    )
    (net (code "72") (name "Net-(R89-Pad2)") (class "Default")
      (node (ref "R89") (pin "2") (pinfunction "2_2") (pintype "passive"))
      (node (ref "R90") (pin "1") (pinfunction "1_1") (pintype "passive"))
    )
    (net (code "73") (name "Net-(R90-Pad2)") (class "Default")
      (node (ref "R90") (pin "2") (pinfunction "2_2") (pintype "passive"))
      (node (ref "R91") (pin "1") (pinfunction "1_1") (pintype "passive"))
    )
    (net (code "74") (name "Net-(R94-Pad2)") (class "Default")
      (node (ref "R94") (pin "2") (pinfunction "2_2") (pintype "passive"))
      (node (ref "R95") (pin "1") (pinfunction "1_1") (pintype "passive"))
    )
    (net (code "75") (name "Net-(R95-Pad2)") (class "Default")
      (node (ref "R95") (pin "2") (pinfunction "2_2") (pintype "passive"))
      (node (ref "R96") (pin "1") (pinfunction "1_1") (pintype "passive"))
    )
    (net (code "76") (name "Net-(R96-Pad2)") (class "Default")
      (node (ref "R96") (pin "2") (pinfunction "2_2") (pintype "passive"))
      (node (ref "R97") (pin "1") (pinfunction "1_1") (pintype "passive"))
    )
    (net (code "77") (name "Net-(R97-Pad2)") (class "Default")
      (node (ref "R97") (pin "2") (pinfunction "2_2") (pintype "passive"))
      (node (ref "R98") (pin "1") (pinfunction "1_1") (pintype "passive"))
    )
    (net (code "78") (name "Net-(R98-Pad2)") (class "Default")
      (node (ref "R98") (pin "2") (pinfunction "2_2") (pintype "passive"))
      (node (ref "R99") (pin "1") (pinfunction "1_1") (pintype "passive"))
    )
    (net (code "79") (name "Net-(R100-Pad1)") (class "Default")
      (node (ref "R100") (pin "1") (pinfunction "1_1") (pintype "passive"))
      (node (ref "R99") (pin "2") (pinfunction "2_2") (pintype "passive"))
    )
    (net (code "80") (name "Net-(R100-Pad2)") (class "Default")
      (node (ref "R100") (pin "2") (pinfunction "2_2") (pintype "passive"))
      (node (ref "R101") (pin "1") (pinfunction "1_1") (pintype "passive"))
    )
    (net (code "81") (name "Net-(R101-Pad2)") (class "Default")
      (node (ref "R101") (pin "2") (pinfunction "2_2") (pintype "passive"))
      (node (ref "R102") (pin "1") (pinfunction "1_1") (pintype "passive"))
    )
    (net (code "82") (name "Net-(R102-Pad2)") (class "Default")
      (node (ref "R102") (pin "2") (pinfunction "2_2") (pintype "passive"))
      (node (ref "R103") (pin "1") (pinfunction "1_1") (pintype "passive"))
    )
    (net (code "83") (name "Net-(R105-Pad2)") (class "Default")
      (node (ref "R105") (pin "2") (pinfunction "2_2") (pintype "passive"))
      (node (ref "R106") (pin "1") (pinfunction "1_1") (pintype "passive"))
    )
    (net (code "84") (name "Net-(R106-Pad2)") (class "Default")
      (node (ref "R106") (pin "2") (pinfunction "2_2") (pintype "passive"))
      (node (ref "R107") (pin "1") (pinfunction "1_1") (pintype "passive"))
    )
    (net (code "85") (name "Net-(R107-Pad2)") (class "Default")
      (node (ref "R107") (pin "2") (pinfunction "2_2") (pintype "passive"))
      (node (ref "R108") (pin "1") (pinfunction "1_1") (pintype "passive"))
    )
    (net (code "86") (name "Net-(R108-Pad2)") (class "Default")
      (node (ref "R108") (pin "2") (pinfunction "2_2") (pintype "passive"))
      (node (ref "R109") (pin "1") (pinfunction "1_1") (pintype "passive"))
    )
    (net (code "87") (name "Net-(R109-Pad2)") (class "Default")
      (node (ref "R109") (pin "2") (pinfunction "2_2") (pintype "passive"))
      (node (ref "R110") (pin "1") (pinfunction "1_1") (pintype "passive"))
    )
    (net (code "88") (name "Net-(R110-Pad2)") (class "Default")
      (node (ref "R110") (pin "2") (pinfunction "2_2") (pintype "passive"))
      (node (ref "R111") (pin "1") (pinfunction "1_1") (pintype "passive"))
    )
    (net (code "89") (name "Net-(R111-Pad2)") (class "Default")
      (node (ref "R111") (pin "2") (pinfunction "2_2") (pintype "passive"))
      (node (ref "R112") (pin "1") (pinfunction "1_1") (pintype "passive"))
    )
    (net (code "90") (name "Net-(R112-Pad2)") (class "Default")
      (node (ref "R112") (pin "2") (pinfunction "2_2") (pintype "passive"))
      (node (ref "R113") (pin "1") (pinfunction "1_1") (pintype "passive"))
    )
    (net (code "91") (name "Net-(R113-Pad2)") (class "Default")
      (node (ref "R113") (pin "2") (pinfunction "2_2") (pintype "passive"))
      (node (ref "R114") (pin "1") (pinfunction "1_1") (pintype "passive"))
    )
    (net (code "92") (name "Net-(R117-Pad2)") (class "Default")
      (node (ref "R117") (pin "2") (pinfunction "2_2") (pintype "passive"))
      (node (ref "R118") (pin "1") (pinfunction "1_1") (pintype "passive"))
    )
    (net (code "93") (name "Net-(R118-Pad2)") (class "Default")
      (node (ref "R118") (pin "2") (pinfunction "2_2") (pintype "passive"))
      (node (ref "R119") (pin "1") (pinfunction "1_1") (pintype "passive"))
    )
    (net (code "94") (name "Net-(R119-Pad2)") (class "Default")
      (node (ref "R119") (pin "2") (pinfunction "2_2") (pintype "passive"))
      (node (ref "R120") (pin "1") (pinfunction "1_1") (pintype "passive"))
    )
    (net (code "95") (name "Net-(R120-Pad2)") (class "Default")
      (node (ref "R120") (pin "2") (pinfunction "2_2") (pintype "passive"))
      (node (ref "R121") (pin "1") (pinfunction "1_1") (pintype "passive"))
    )
    (net (code "96") (name "Net-(R121-Pad2)") (class "Default")
      (node (ref "R121") (pin "2") (pinfunction "2_2") (pintype "passive"))
      (node (ref "R122") (pin "1") (pinfunction "1_1") (pintype "passive"))
    )
    (net (code "97") (name "Net-(R122-Pad2)") (class "Default")
      (node (ref "R122") (pin "2") (pinfunction "2_2") (pintype "passive"))
      (node (ref "R123") (pin "1") (pinfunction "1_1") (pintype "passive"))
    )
    (net (code "98") (name "Net-(R123-Pad2)") (class "Default")
      (node (ref "R123") (pin "2") (pinfunction "2_2") (pintype "passive"))
      (node (ref "R124") (pin "1") (pinfunction "1_1") (pintype "passive"))
    )
    (net (code "99") (name "Net-(R124-Pad2)") (class "Default")
      (node (ref "R124") (pin "2") (pinfunction "2_2") (pintype "passive"))
      (node (ref "R125") (pin "1") (pinfunction "1_1") (pintype "passive"))
    )
    (net (code "100") (name "Net-(R125-Pad2)") (class "Default")
      (node (ref "R125") (pin "2") (pinfunction "2_2") (pintype "passive"))
      (node (ref "R126") (pin "1") (pinfunction "1_1") (pintype "passive"))
    )
    (net (code "101") (name "Net-(R128-Pad2)") (class "Default")
      (node (ref "R128") (pin "2") (pinfunction "2_2") (pintype "passive"))
      (node (ref "R129") (pin "1") (pinfunction "1_1") (pintype "passive"))
    )
    (net (code "102") (name "Net-(R129-Pad2)") (class "Default")
      (node (ref "R129") (pin "2") (pinfunction "2_2") (pintype "passive"))
      (node (ref "R130") (pin "1") (pinfunction "1_1") (pintype "passive"))
    )
    (net (code "103") (name "Net-(R130-Pad2)") (class "Default")
      (node (ref "R130") (pin "2") (pinfunction "2_2") (pintype "passive"))
      (node (ref "R131") (pin "1") (pinfunction "1_1") (pintype "passive"))
    )
    (net (code "104") (name "Net-(R131-Pad2)") (class "Default")
      (node (ref "R131") (pin "2") (pinfunction "2_2") (pintype "passive"))
      (node (ref "R132") (pin "1") (pinfunction "1_1") (pintype "passive"))
    )
    (net (code "105") (name "Net-(R132-Pad2)") (class "Default")
      (node (ref "R132") (pin "2") (pinfunction "2_2") (pintype "passive"))
      (node (ref "R133") (pin "1") (pinfunction "1_1") (pintype "passive"))
    )
    (net (code "106") (name "Net-(R133-Pad2)") (class "Default")
      (node (ref "R133") (pin "2") (pinfunction "2_2") (pintype "passive"))
      (node (ref "R134") (pin "1") (pinfunction "1_1") (pintype "passive"))
    )
    (net (code "107") (name "Net-(R134-Pad2)") (class "Default")
      (node (ref "R134") (pin "2") (pinfunction "2_2") (pintype "passive"))
      (node (ref "R135") (pin "1") (pinfunction "1_1") (pintype "passive"))
    )
    (net (code "108") (name "Net-(R135-Pad2)") (class "Default")
      (node (ref "R135") (pin "2") (pinfunction "2_2") (pintype "passive"))
      (node (ref "R136") (pin "1") (pinfunction "1_1") (pintype "passive"))
    )
    (net (code "109") (name "Net-(R136-Pad2)") (class "Default")
      (node (ref "R136") (pin "2") (pinfunction "2_2") (pintype "passive"))
      (node (ref "R137") (pin "1") (pinfunction "1_1") (pintype "passive"))
    )
    (net (code "110") (name "Net-(R140-Pad2)") (class "Default")
      (node (ref "R140") (pin "2") (pinfunction "2_2") (pintype "passive"))
      (node (ref "R141") (pin "1") (pinfunction "1_1") (pintype "passive"))
    )
    (net (code "111") (name "Net-(R141-Pad2)") (class "Default")
      (node (ref "R141") (pin "2") (pinfunction "2_2") (pintype "passive"))
      (node (ref "R142") (pin "1") (pinfunction "1_1") (pintype "passive"))
    )
    (net (code "112") (name "Net-(R142-Pad2)") (class "Default")
      (node (ref "R142") (pin "2") (pinfunction "2_2") (pintype "passive"))
      (node (ref "R143") (pin "1") (pinfunction "1_1") (pintype "passive"))
    )
    (net (code "113") (name "Net-(R143-Pad2)") (class "Default")
      (node (ref "R143") (pin "2") (pinfunction "2_2") (pintype "passive"))
      (node (ref "R144") (pin "1") (pinfunction "1_1") (pintype "passive"))
    )
    (net (code "114") (name "Net-(R144-Pad2)") (class "Default")
      (node (ref "R144") (pin "2") (pinfunction "2_2") (pintype "passive"))
      (node (ref "R145") (pin "1") (pinfunction "1_1") (pintype "passive"))
    )
    (net (code "115") (name "Net-(R145-Pad2)") (class "Default")
      (node (ref "R145") (pin "2") (pinfunction "2_2") (pintype "passive"))
      (node (ref "R146") (pin "1") (pinfunction "1_1") (pintype "passive"))
    )
    (net (code "116") (name "Net-(R146-Pad2)") (class "Default")
      (node (ref "R146") (pin "2") (pinfunction "2_2") (pintype "passive"))
      (node (ref "R147") (pin "1") (pinfunction "1_1") (pintype "passive"))
    )
    (net (code "117") (name "Net-(R147-Pad2)") (class "Default")
      (node (ref "R147") (pin "2") (pinfunction "2_2") (pintype "passive"))
      (node (ref "R148") (pin "1") (pinfunction "1_1") (pintype "passive"))
    )
    (net (code "118") (name "Net-(R148-Pad2)") (class "Default")
      (node (ref "R148") (pin "2") (pinfunction "2_2") (pintype "passive"))
      (node (ref "R149") (pin "1") (pinfunction "1_1") (pintype "passive"))
    )
    (net (code "119") (name "Net-(R151-Pad2)") (class "Default")
      (node (ref "R151") (pin "2") (pinfunction "2_2") (pintype "passive"))
      (node (ref "R152") (pin "1") (pinfunction "1_1") (pintype "passive"))
    )
    (net (code "120") (name "Net-(R152-Pad2)") (class "Default")
      (node (ref "R152") (pin "2") (pinfunction "2_2") (pintype "passive"))
      (node (ref "R153") (pin "1") (pinfunction "1_1") (pintype "passive"))
    )
    (net (code "121") (name "Net-(R153-Pad2)") (class "Default")
      (node (ref "R153") (pin "2") (pinfunction "2_2") (pintype "passive"))
      (node (ref "R154") (pin "1") (pinfunction "1_1") (pintype "passive"))
    )
    (net (code "122") (name "Net-(R154-Pad2)") (class "Default")
      (node (ref "R154") (pin "2") (pinfunction "2_2") (pintype "passive"))
      (node (ref "R155") (pin "1") (pinfunction "1_1") (pintype "passive"))
    )
    (net (code "123") (name "Net-(R155-Pad2)") (class "Default")
      (node (ref "R155") (pin "2") (pinfunction "2_2") (pintype "passive"))
      (node (ref "R156") (pin "1") (pinfunction "1_1") (pintype "passive"))
    )
    (net (code "124") (name "Net-(R156-Pad2)") (class "Default")
      (node (ref "R156") (pin "2") (pinfunction "2_2") (pintype "passive"))
      (node (ref "R157") (pin "1") (pinfunction "1_1") (pintype "passive"))
    )
    (net (code "125") (name "Net-(R157-Pad2)") (class "Default")
      (node (ref "R157") (pin "2") (pinfunction "2_2") (pintype "passive"))
      (node (ref "R158") (pin "1") (pinfunction "1_1") (pintype "passive"))
    )
    (net (code "126") (name "Net-(R158-Pad2)") (class "Default")
      (node (ref "R158") (pin "2") (pinfunction "2_2") (pintype "passive"))
      (node (ref "R159") (pin "1") (pinfunction "1_1") (pintype "passive"))
    )
    (net (code "127") (name "Net-(R159-Pad2)") (class "Default")
      (node (ref "R159") (pin "2") (pinfunction "2_2") (pintype "passive"))
      (node (ref "R160") (pin "1") (pinfunction "1_1") (pintype "passive"))
    )
    (net (code "128") (name "Net-(R163-Pad2)") (class "Default")
      (node (ref "R163") (pin "2") (pinfunction "2_2") (pintype "passive"))
      (node (ref "R164") (pin "1") (pinfunction "1_1") (pintype "passive"))
    )
    (net (code "129") (name "Net-(R164-Pad2)") (class "Default")
      (node (ref "R164") (pin "2") (pinfunction "2_2") (pintype "passive"))
      (node (ref "R165") (pin "1") (pinfunction "1_1") (pintype "passive"))
    )
    (net (code "130") (name "Net-(R165-Pad2)") (class "Default")
      (node (ref "R165") (pin "2") (pinfunction "2_2") (pintype "passive"))
      (node (ref "R166") (pin "1") (pinfunction "1_1") (pintype "passive"))
    )
    (net (code "131") (name "Net-(R166-Pad2)") (class "Default")
      (node (ref "R166") (pin "2") (pinfunction "2_2") (pintype "passive"))
      (node (ref "R167") (pin "1") (pinfunction "1_1") (pintype "passive"))
    )
    (net (code "132") (name "Net-(R167-Pad2)") (class "Default")
      (node (ref "R167") (pin "2") (pinfunction "2_2") (pintype "passive"))
      (node (ref "R168") (pin "1") (pinfunction "1_1") (pintype "passive"))
    )
    (net (code "133") (name "Net-(R168-Pad2)") (class "Default")
      (node (ref "R168") (pin "2") (pinfunction "2_2") (pintype "passive"))
      (node (ref "R169") (pin "1") (pinfunction "1_1") (pintype "passive"))
    )
    (net (code "134") (name "Net-(R169-Pad2)") (class "Default")
      (node (ref "R169") (pin "2") (pinfunction "2_2") (pintype "passive"))
      (node (ref "R170") (pin "1") (pinfunction "1_1") (pintype "passive"))
    )
    (net (code "135") (name "Net-(R170-Pad2)") (class "Default")
      (node (ref "R170") (pin "2") (pinfunction "2_2") (pintype "passive"))
      (node (ref "R171") (pin "1") (pinfunction "1_1") (pintype "passive"))
    )
    (net (code "136") (name "Net-(R171-Pad2)") (class "Default")
      (node (ref "R171") (pin "2") (pinfunction "2_2") (pintype "passive"))
      (node (ref "R172") (pin "1") (pinfunction "1_1") (pintype "passive"))
    )
    (net (code "137") (name "Net-(R174-Pad2)") (class "Default")
      (node (ref "R174") (pin "2") (pinfunction "2_2") (pintype "passive"))
      (node (ref "R175") (pin "1") (pinfunction "1_1") (pintype "passive"))
    )
    (net (code "138") (name "Net-(R175-Pad2)") (class "Default")
      (node (ref "R175") (pin "2") (pinfunction "2_2") (pintype "passive"))
      (node (ref "R176") (pin "1") (pinfunction "1_1") (pintype "passive"))
    )
    (net (code "139") (name "Net-(R176-Pad2)") (class "Default")
      (node (ref "R176") (pin "2") (pinfunction "2_2") (pintype "passive"))
      (node (ref "R177") (pin "1") (pinfunction "1_1") (pintype "passive"))
    )
    (net (code "140") (name "Net-(R177-Pad2)") (class "Default")
      (node (ref "R177") (pin "2") (pinfunction "2_2") (pintype "passive"))
      (node (ref "R178") (pin "1") (pinfunction "1_1") (pintype "passive"))
    )
    (net (code "141") (name "Net-(R178-Pad2)") (class "Default")
      (node (ref "R178") (pin "2") (pinfunction "2_2") (pintype "passive"))
      (node (ref "R179") (pin "1") (pinfunction "1_1") (pintype "passive"))
    )
    (net (code "142") (name "Net-(R179-Pad2)") (class "Default")
      (node (ref "R179") (pin "2") (pinfunction "2_2") (pintype "passive"))
      (node (ref "R180") (pin "1") (pinfunction "1_1") (pintype "passive"))
    )
    (net (code "143") (name "Net-(R180-Pad2)") (class "Default")
      (node (ref "R180") (pin "2") (pinfunction "2_2") (pintype "passive"))
      (node (ref "R181") (pin "1") (pinfunction "1_1") (pintype "passive"))
    )
    (net (code "144") (name "Net-(R181-Pad2)") (class "Default")
      (node (ref "R181") (pin "2") (pinfunction "2_2") (pintype "passive"))
      (node (ref "R182") (pin "1") (pinfunction "1_1") (pintype "passive"))
    )
    (net (code "145") (name "Net-(R182-Pad2)") (class "Default")
      (node (ref "R182") (pin "2") (pinfunction "2_2") (pintype "passive"))
      (node (ref "R183") (pin "1") (pinfunction "1_1") (pintype "passive"))
    )
    (net (code "146") (name "Net-(R186-Pad2)") (class "Default")
      (node (ref "R186") (pin "2") (pinfunction "2_2") (pintype "passive"))
      (node (ref "R187") (pin "1") (pinfunction "1_1") (pintype "passive"))
    )
    (net (code "147") (name "Net-(R187-Pad2)") (class "Default")
      (node (ref "R187") (pin "2") (pinfunction "2_2") (pintype "passive"))
      (node (ref "R188") (pin "1") (pinfunction "1_1") (pintype "passive"))
    )
    (net (code "148") (name "Net-(R188-Pad2)") (class "Default")
      (node (ref "R188") (pin "2") (pinfunction "2_2") (pintype "passive"))
      (node (ref "R189") (pin "1") (pinfunction "1_1") (pintype "passive"))
    )
    (net (code "149") (name "Net-(R189-Pad2)") (class "Default")
      (node (ref "R189") (pin "2") (pinfunction "2_2") (pintype "passive"))
      (node (ref "R190") (pin "1") (pinfunction "1_1") (pintype "passive"))
    )
    (net (code "150") (name "Net-(R190-Pad2)") (class "Default")
      (node (ref "R190") (pin "2") (pinfunction "2_2") (pintype "passive"))
      (node (ref "R191") (pin "1") (pinfunction "1_1") (pintype "passive"))
    )
    (net (code "151") (name "Net-(R191-Pad2)") (class "Default")
      (node (ref "R191") (pin "2") (pinfunction "2_2") (pintype "passive"))
      (node (ref "R192") (pin "1") (pinfunction "1_1") (pintype "passive"))
    )
    (net (code "152") (name "Net-(R192-Pad2)") (class "Default")
      (node (ref "R192") (pin "2") (pinfunction "2_2") (pintype "passive"))
      (node (ref "R193") (pin "1") (pinfunction "1_1") (pintype "passive"))
    )
    (net (code "153") (name "Net-(R193-Pad2)") (class "Default")
      (node (ref "R193") (pin "2") (pinfunction "2_2") (pintype "passive"))
      (node (ref "R194") (pin "1") (pinfunction "1_1") (pintype "passive"))
    )
    (net (code "154") (name "Net-(R194-Pad2)") (class "Default")
      (node (ref "R194") (pin "2") (pinfunction "2_2") (pintype "passive"))
      (node (ref "R195") (pin "1") (pinfunction "1_1") (pintype "passive"))
    )
    (net (code "155") (name "Net-(R197-Pad2)") (class "Default")
      (node (ref "R197") (pin "2") (pinfunction "2_2") (pintype "passive"))
      (node (ref "R198") (pin "1") (pinfunction "1_1") (pintype "passive"))
    )
    (net (code "156") (name "Net-(R198-Pad2)") (class "Default")
      (node (ref "R198") (pin "2") (pinfunction "2_2") (pintype "passive"))
      (node (ref "R199") (pin "1") (pinfunction "1_1") (pintype "passive"))
    )
    (net (code "157") (name "Net-(R199-Pad2)") (class "Default")
      (node (ref "R199") (pin "2") (pinfunction "2_2") (pintype "passive"))
      (node (ref "R200") (pin "1") (pinfunction "1_1") (pintype "passive"))
    )
    (net (code "158") (name "Net-(R200-Pad2)") (class "Default")
      (node (ref "R200") (pin "2") (pinfunction "2_2") (pintype "passive"))
      (node (ref "R201") (pin "1") (pinfunction "1_1") (pintype "passive"))
    )
    (net (code "159") (name "Net-(R201-Pad2)") (class "Default")
      (node (ref "R201") (pin "2") (pinfunction "2_2") (pintype "passive"))
      (node (ref "R202") (pin "1") (pinfunction "1_1") (pintype "passive"))
    )
    (net (code "160") (name "Net-(R202-Pad2)") (class "Default")
      (node (ref "R202") (pin "2") (pinfunction "2_2") (pintype "passive"))
      (node (ref "R203") (pin "1") (pinfunction "1_1") (pintype "passive"))
    )
    (net (code "161") (name "Net-(R203-Pad2)") (class "Default")
      (node (ref "R203") (pin "2") (pinfunction "2_2") (pintype "passive"))
      (node (ref "R204") (pin "1") (pinfunction "1_1") (pintype "passive"))
    )
    (net (code "162") (name "Net-(R204-Pad2)") (class "Default")
      (node (ref "R204") (pin "2") (pinfunction "2_2") (pintype "passive"))
      (node (ref "R205") (pin "1") (pinfunction "1_1") (pintype "passive"))
    )
    (net (code "163") (name "Net-(R205-Pad2)") (class "Default")
      (node (ref "R205") (pin "2") (pinfunction "2_2") (pintype "passive"))
      (node (ref "R206") (pin "1") (pinfunction "1_1") (pintype "passive"))
    )
    (net (code "164") (name "unconnected-(X1A-KL-Pad1)") (class "Default")
      (node (ref "X1") (pin "1") (pinfunction "KL_1") (pintype "passive"))
    )
    (net (code "165") (name "unconnected-(X2B-KL-Pad2)") (class "Default")
      (node (ref "X2") (pin "2") (pinfunction "KL_2") (pintype "passive"))
    )
    (net (code "166") (name "unconnected-(X5A-KL-Pad1)") (class "Default")
      (node (ref "X5") (pin "1") (pinfunction "KL_1") (pintype "passive"))
    )
    (net (code "167") (name "unconnected-(X6B-KL-Pad2)") (class "Default")
      (node (ref "X6") (pin "2") (pinfunction "KL_2") (pintype "passive"))
    )
    (net (code "168") (name "unconnected-(X7A-KL-Pad1)") (class "Default")
      (node (ref "X7") (pin "1") (pinfunction "KL_1") (pintype "passive"))
    )
    (net (code "169") (name "unconnected-(X8B-KL-Pad2)") (class "Default")
      (node (ref "X8") (pin "2") (pinfunction "KL_2") (pintype "passive"))
    )
    (net (code "170") (name "unconnected-(X9A-KL-Pad1)") (class "Default")
      (node (ref "X9") (pin "1") (pinfunction "KL_1") (pintype "passive"))
    )
    (net (code "171") (name "unconnected-(X10B-KL-Pad2)") (class "Default")
      (node (ref "X10") (pin "2") (pinfunction "KL_2") (pintype "passive"))
    )
    (net (code "172") (name "unconnected-(X11A-KL-Pad1)") (class "Default")
      (node (ref "X11") (pin "1") (pinfunction "KL_1") (pintype "passive"))
    )
    (net (code "173") (name "unconnected-(X12B-KL-Pad2)") (class "Default")
      (node (ref "X12") (pin "2") (pinfunction "KL_2") (pintype "passive"))
    )
    (net (code "174") (name "unconnected-(X13A-KL-Pad1)") (class "Default")
      (node (ref "X13") (pin "1") (pinfunction "KL_1") (pintype "passive"))
    )
    (net (code "175") (name "unconnected-(X14B-KL-Pad2)") (class "Default")
      (node (ref "X14") (pin "2") (pinfunction "KL_2") (pintype "passive"))
    )
    (net (code "176") (name "unconnected-(X15A-KL-Pad1)") (class "Default")
      (node (ref "X15") (pin "1") (pinfunction "KL_1") (pintype "passive"))
    )
    (net (code "177") (name "unconnected-(X16B-KL-Pad2)") (class "Default")
      (node (ref "X16") (pin "2") (pinfunction "KL_2") (pintype "passive"))
    )
    (net (code "178") (name "unconnected-(X17A-KL-Pad1)") (class "Default")
      (node (ref "X17") (pin "1") (pinfunction "KL_1") (pintype "passive"))
    )
    (net (code "179") (name "unconnected-(X18B-KL-Pad2)") (class "Default")
      (node (ref "X18") (pin "2") (pinfunction "KL_2") (pintype "passive"))
    )
  )
)
